# trig3_board.net
KiCad netlist of a schematic drawn in EAGLE
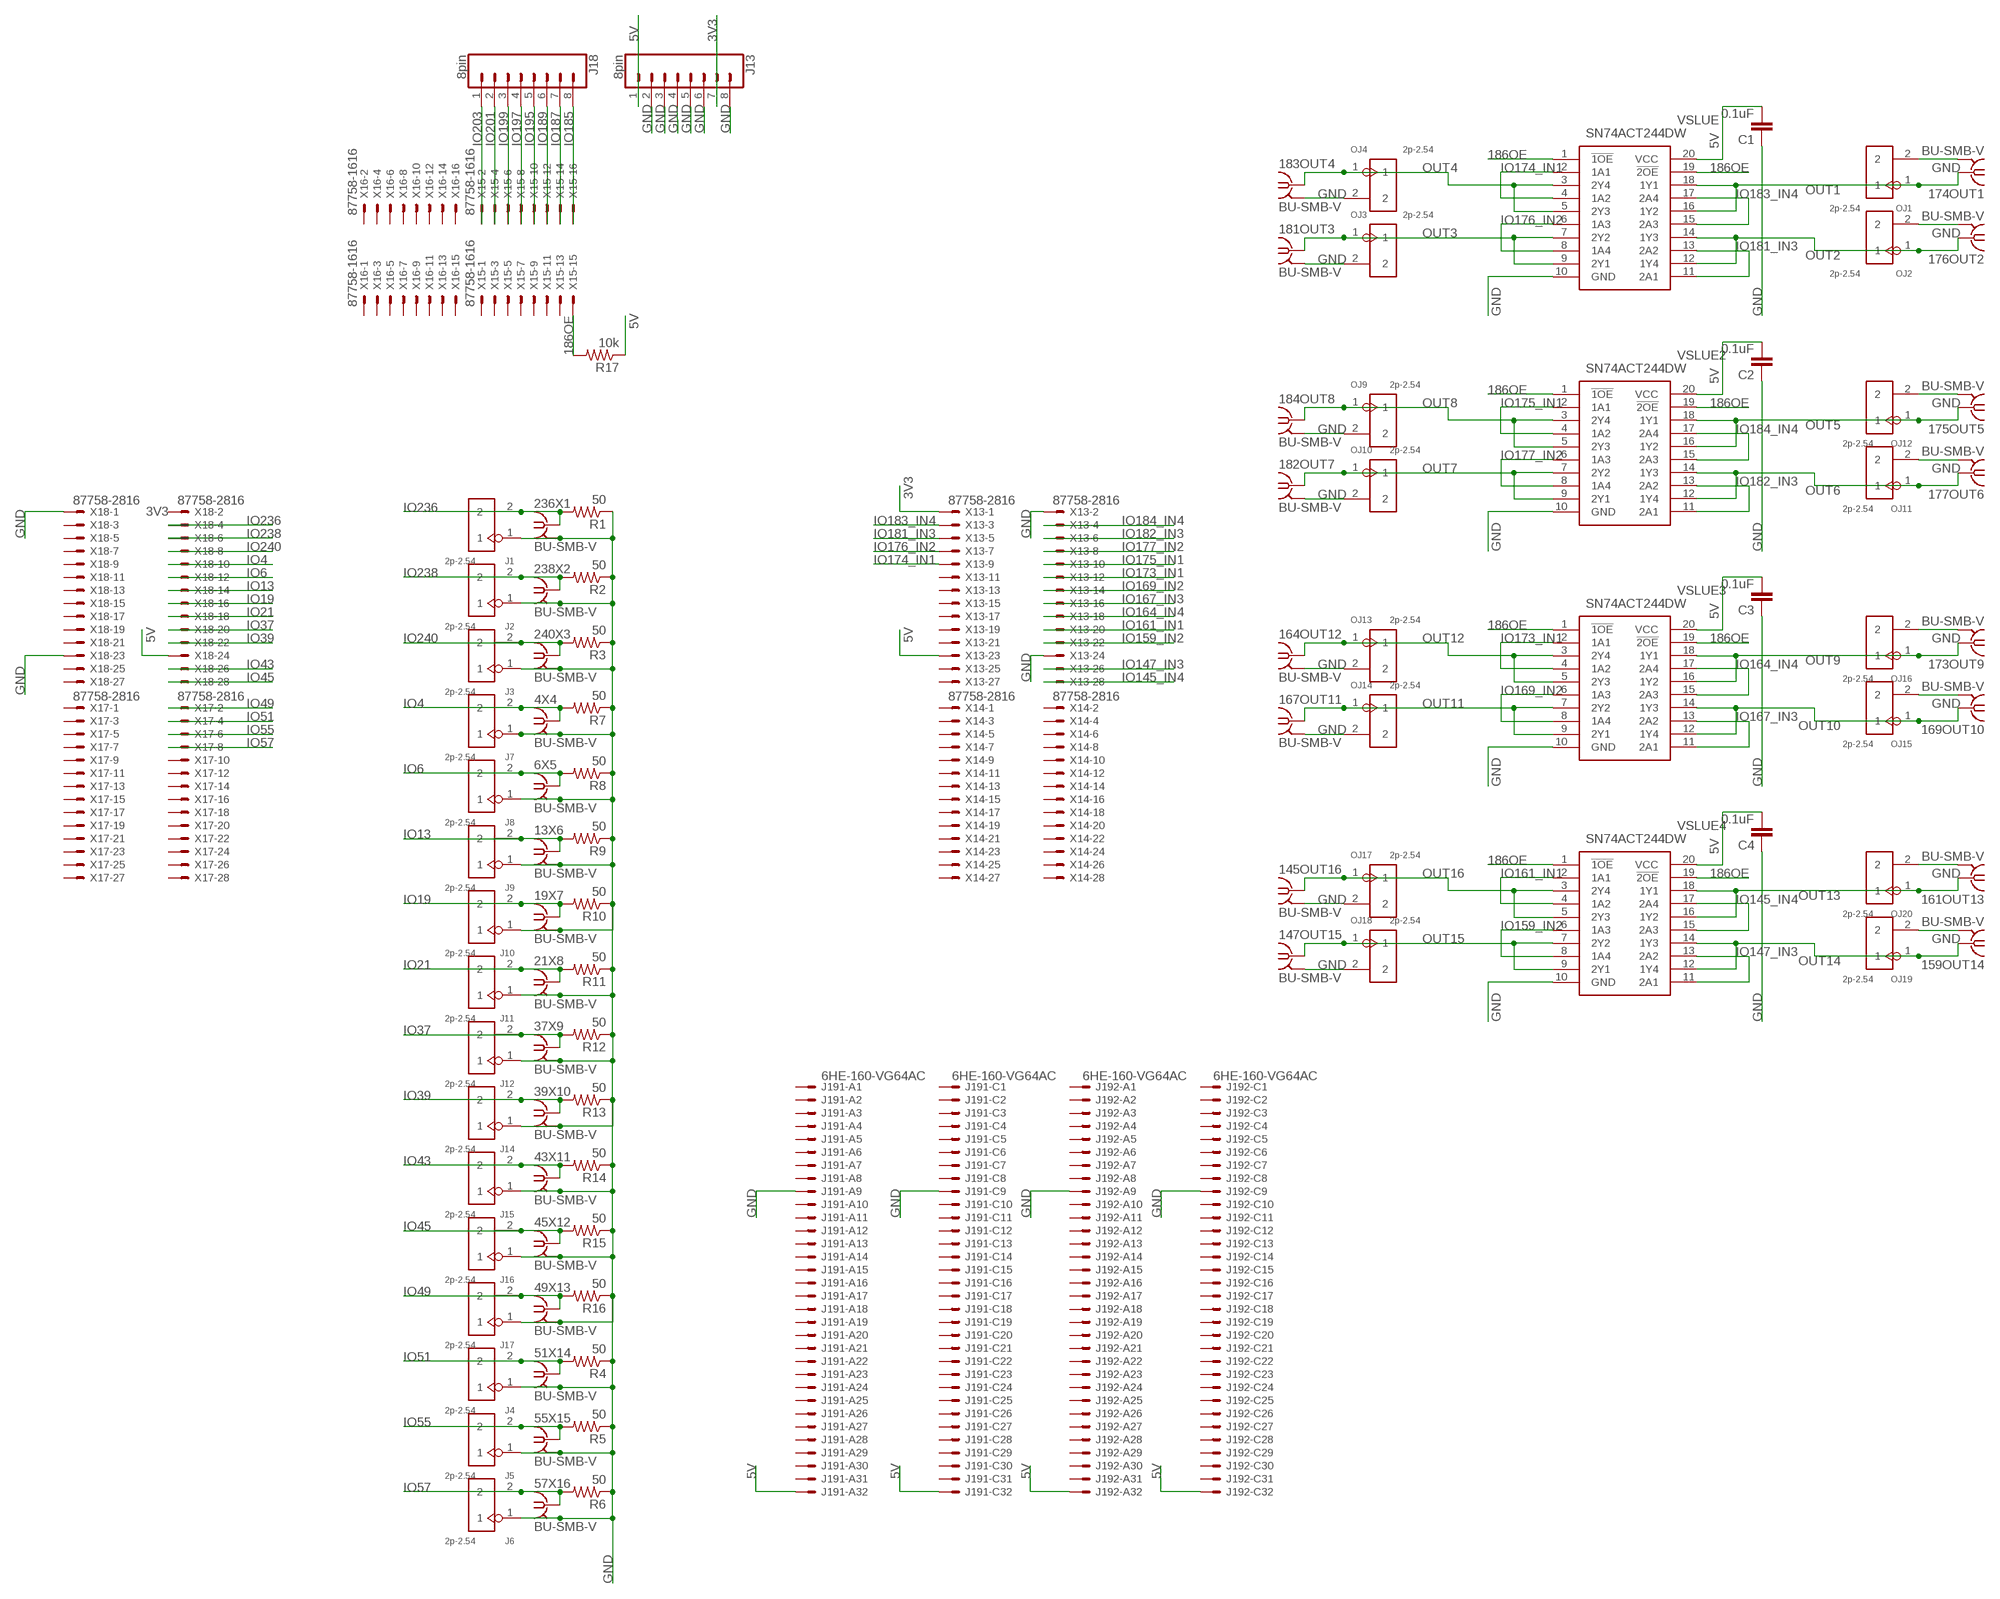
[diagram p0: schematic, sheet 1]

(export (version "E")
  (design (tool "Eeschema 10.0.6"))
  (components
    (comp (ref "4X4")
      (value "BU-SMB-V")
      (footprint "eagle-import:BU-SMB-V")
      (libsource (lib "eagle-import") (part "BU-SMB-V"))
    )
    (comp (ref "6X5")
      (value "BU-SMB-V")
      (footprint "eagle-import:BU-SMB-V")
      (libsource (lib "eagle-import") (part "BU-SMB-V"))
    )
    (comp (ref "13X6")
      (value "BU-SMB-V")
      (footprint "eagle-import:BU-SMB-V")
      (libsource (lib "eagle-import") (part "BU-SMB-V"))
    )
    (comp (ref "19X7")
      (value "BU-SMB-V")
      (footprint "eagle-import:BU-SMB-V")
      (libsource (lib "eagle-import") (part "BU-SMB-V"))
    )
    (comp (ref "21X8")
      (value "BU-SMB-V")
      (footprint "eagle-import:BU-SMB-V")
      (libsource (lib "eagle-import") (part "BU-SMB-V"))
    )
    (comp (ref "37X9")
      (value "BU-SMB-V")
      (footprint "eagle-import:BU-SMB-V")
      (libsource (lib "eagle-import") (part "BU-SMB-V"))
    )
    (comp (ref "39X10")
      (value "BU-SMB-V")
      (footprint "eagle-import:BU-SMB-V")
      (libsource (lib "eagle-import") (part "BU-SMB-V"))
    )
    (comp (ref "43X11")
      (value "BU-SMB-V")
      (footprint "eagle-import:BU-SMB-V")
      (libsource (lib "eagle-import") (part "BU-SMB-V"))
    )
    (comp (ref "45X12")
      (value "BU-SMB-V")
      (footprint "eagle-import:BU-SMB-V")
      (libsource (lib "eagle-import") (part "BU-SMB-V"))
    )
    (comp (ref "49X13")
      (value "BU-SMB-V")
      (footprint "eagle-import:BU-SMB-V")
      (libsource (lib "eagle-import") (part "BU-SMB-V"))
    )
    (comp (ref "51X14")
      (value "BU-SMB-V")
      (footprint "eagle-import:BU-SMB-V")
      (libsource (lib "eagle-import") (part "BU-SMB-V"))
    )
    (comp (ref "55X15")
      (value "BU-SMB-V")
      (footprint "eagle-import:BU-SMB-V")
      (libsource (lib "eagle-import") (part "BU-SMB-V"))
    )
    (comp (ref "57X16")
      (value "BU-SMB-V")
      (footprint "eagle-import:BU-SMB-V")
      (libsource (lib "eagle-import") (part "BU-SMB-V"))
    )
    (comp (ref "145OUT16")
      (value "BU-SMB-V")
      (footprint "eagle-import:BU-SMB-V")
      (libsource (lib "eagle-import") (part "BU-SMB-V"))
    )
    (comp (ref "147OUT15")
      (value "BU-SMB-V")
      (footprint "eagle-import:BU-SMB-V")
      (libsource (lib "eagle-import") (part "BU-SMB-V"))
    )
    (comp (ref "159OUT14")
      (value "BU-SMB-V")
      (footprint "eagle-import:BU-SMB-V")
      (libsource (lib "eagle-import") (part "BU-SMB-V"))
    )
    (comp (ref "161OUT13")
      (value "BU-SMB-V")
      (footprint "eagle-import:BU-SMB-V")
      (libsource (lib "eagle-import") (part "BU-SMB-V"))
    )
    (comp (ref "164OUT12")
      (value "BU-SMB-V")
      (footprint "eagle-import:BU-SMB-V")
      (libsource (lib "eagle-import") (part "BU-SMB-V"))
    )
    (comp (ref "167OUT11")
      (value "BU-SMB-V")
      (footprint "eagle-import:BU-SMB-V")
      (libsource (lib "eagle-import") (part "BU-SMB-V"))
    )
    (comp (ref "169OUT10")
      (value "BU-SMB-V")
      (footprint "eagle-import:BU-SMB-V")
      (libsource (lib "eagle-import") (part "BU-SMB-V"))
    )
    (comp (ref "173OUT9")
      (value "BU-SMB-V")
      (footprint "eagle-import:BU-SMB-V")
      (libsource (lib "eagle-import") (part "BU-SMB-V"))
    )
    (comp (ref "174OUT1")
      (value "BU-SMB-V")
      (footprint "eagle-import:BU-SMB-V")
      (libsource (lib "eagle-import") (part "BU-SMB-V"))
    )
    (comp (ref "175OUT5")
      (value "BU-SMB-V")
      (footprint "eagle-import:BU-SMB-V")
      (libsource (lib "eagle-import") (part "BU-SMB-V"))
    )
    (comp (ref "176OUT2")
      (value "BU-SMB-V")
      (footprint "eagle-import:BU-SMB-V")
      (libsource (lib "eagle-import") (part "BU-SMB-V"))
    )
    (comp (ref "177OUT6")
      (value "BU-SMB-V")
      (footprint "eagle-import:BU-SMB-V")
      (libsource (lib "eagle-import") (part "BU-SMB-V"))
    )
    (comp (ref "181OUT3")
      (value "BU-SMB-V")
      (footprint "eagle-import:BU-SMB-V")
      (libsource (lib "eagle-import") (part "BU-SMB-V"))
    )
    (comp (ref "182OUT7")
      (value "BU-SMB-V")
      (footprint "eagle-import:BU-SMB-V")
      (libsource (lib "eagle-import") (part "BU-SMB-V"))
    )
    (comp (ref "183OUT4")
      (value "BU-SMB-V")
      (footprint "eagle-import:BU-SMB-V")
      (libsource (lib "eagle-import") (part "BU-SMB-V"))
    )
    (comp (ref "184OUT8")
      (value "BU-SMB-V")
      (footprint "eagle-import:BU-SMB-V")
      (libsource (lib "eagle-import") (part "BU-SMB-V"))
    )
    (comp (ref "236X1")
      (value "BU-SMB-V")
      (footprint "eagle-import:BU-SMB-V")
      (libsource (lib "eagle-import") (part "BU-SMB-V"))
    )
    (comp (ref "238X2")
      (value "BU-SMB-V")
      (footprint "eagle-import:BU-SMB-V")
      (libsource (lib "eagle-import") (part "BU-SMB-V"))
    )
    (comp (ref "240X3")
      (value "BU-SMB-V")
      (footprint "eagle-import:BU-SMB-V")
      (libsource (lib "eagle-import") (part "BU-SMB-V"))
    )
    (comp (ref "C1")
      (value "0.1uF")
      (footprint "eagle-import:0805")
      (libsource (lib "eagle-import") (part "CAP0805"))
    )
    (comp (ref "C2")
      (value "0.1uF")
      (footprint "eagle-import:0805")
      (libsource (lib "eagle-import") (part "CAP0805"))
    )
    (comp (ref "C3")
      (value "0.1uF")
      (footprint "eagle-import:0805")
      (libsource (lib "eagle-import") (part "CAP0805"))
    )
    (comp (ref "C4")
      (value "0.1uF")
      (footprint "eagle-import:0805")
      (libsource (lib "eagle-import") (part "CAP0805"))
    )
    (comp (ref "J1")
      (value "2p-2.54")
      (footprint "eagle-import:H2-2.54")
      (fields (field (name "MPN") "P125-1102A0BS116A1"))
      (libsource (lib "eagle-import") (part "DIP-BLACK-MALE-HEADER-VERT(2P-2.54)"))
    )
    (comp (ref "J2")
      (value "2p-2.54")
      (footprint "eagle-import:H2-2.54")
      (fields (field (name "MPN") "P125-1102A0BS116A1"))
      (libsource (lib "eagle-import") (part "DIP-BLACK-MALE-HEADER-VERT(2P-2.54)"))
    )
    (comp (ref "J3")
      (value "2p-2.54")
      (footprint "eagle-import:H2-2.54")
      (fields (field (name "MPN") "P125-1102A0BS116A1"))
      (libsource (lib "eagle-import") (part "DIP-BLACK-MALE-HEADER-VERT(2P-2.54)"))
    )
    (comp (ref "J4")
      (value "2p-2.54")
      (footprint "eagle-import:H2-2.54")
      (fields (field (name "MPN") "P125-1102A0BS116A1"))
      (libsource (lib "eagle-import") (part "DIP-BLACK-MALE-HEADER-VERT(2P-2.54)"))
    )
    (comp (ref "J5")
      (value "2p-2.54")
      (footprint "eagle-import:H2-2.54")
      (fields (field (name "MPN") "P125-1102A0BS116A1"))
      (libsource (lib "eagle-import") (part "DIP-BLACK-MALE-HEADER-VERT(2P-2.54)"))
    )
    (comp (ref "J6")
      (value "2p-2.54")
      (footprint "eagle-import:H2-2.54")
      (fields (field (name "MPN") "P125-1102A0BS116A1"))
      (libsource (lib "eagle-import") (part "DIP-BLACK-MALE-HEADER-VERT(2P-2.54)"))
    )
    (comp (ref "J7")
      (value "2p-2.54")
      (footprint "eagle-import:H2-2.54")
      (fields (field (name "MPN") "P125-1102A0BS116A1"))
      (libsource (lib "eagle-import") (part "DIP-BLACK-MALE-HEADER-VERT(2P-2.54)"))
    )
    (comp (ref "J8")
      (value "2p-2.54")
      (footprint "eagle-import:H2-2.54")
      (fields (field (name "MPN") "P125-1102A0BS116A1"))
      (libsource (lib "eagle-import") (part "DIP-BLACK-MALE-HEADER-VERT(2P-2.54)"))
    )
    (comp (ref "J9")
      (value "2p-2.54")
      (footprint "eagle-import:H2-2.54")
      (fields (field (name "MPN") "P125-1102A0BS116A1"))
      (libsource (lib "eagle-import") (part "DIP-BLACK-MALE-HEADER-VERT(2P-2.54)"))
    )
    (comp (ref "J10")
      (value "2p-2.54")
      (footprint "eagle-import:H2-2.54")
      (fields (field (name "MPN") "P125-1102A0BS116A1"))
      (libsource (lib "eagle-import") (part "DIP-BLACK-MALE-HEADER-VERT(2P-2.54)"))
    )
    (comp (ref "J11")
      (value "2p-2.54")
      (footprint "eagle-import:H2-2.54")
      (fields (field (name "MPN") "P125-1102A0BS116A1"))
      (libsource (lib "eagle-import") (part "DIP-BLACK-MALE-HEADER-VERT(2P-2.54)"))
    )
    (comp (ref "J12")
      (value "2p-2.54")
      (footprint "eagle-import:H2-2.54")
      (fields (field (name "MPN") "P125-1102A0BS116A1"))
      (libsource (lib "eagle-import") (part "DIP-BLACK-MALE-HEADER-VERT(2P-2.54)"))
    )
    (comp (ref "J13")
      (value "8pin")
      (footprint "eagle-import:1X08")
      (libsource (lib "eagle-import") (part "CONN_08{dblquote}"))
    )
    (comp (ref "J14")
      (value "2p-2.54")
      (footprint "eagle-import:H2-2.54")
      (fields (field (name "MPN") "P125-1102A0BS116A1"))
      (libsource (lib "eagle-import") (part "DIP-BLACK-MALE-HEADER-VERT(2P-2.54)"))
    )
    (comp (ref "J15")
      (value "2p-2.54")
      (footprint "eagle-import:H2-2.54")
      (fields (field (name "MPN") "P125-1102A0BS116A1"))
      (libsource (lib "eagle-import") (part "DIP-BLACK-MALE-HEADER-VERT(2P-2.54)"))
    )
    (comp (ref "J16")
      (value "2p-2.54")
      (footprint "eagle-import:H2-2.54")
      (fields (field (name "MPN") "P125-1102A0BS116A1"))
      (libsource (lib "eagle-import") (part "DIP-BLACK-MALE-HEADER-VERT(2P-2.54)"))
    )
    (comp (ref "J17")
      (value "2p-2.54")
      (footprint "eagle-import:H2-2.54")
      (fields (field (name "MPN") "P125-1102A0BS116A1"))
      (libsource (lib "eagle-import") (part "DIP-BLACK-MALE-HEADER-VERT(2P-2.54)"))
    )
    (comp (ref "J18")
      (value "8pin")
      (footprint "eagle-import:1X08")
      (libsource (lib "eagle-import") (part "CONN_08{dblquote}"))
    )
    (comp (ref "J19")
      (value "6HE-160-VG64AC")
      (footprint "eagle-import:6HE_160-VG64AC")
      (libsource (lib "eagle-import") (part "6HE-?-VG64AC160"))
    )
    (comp (ref "OJ1")
      (value "2p-2.54")
      (footprint "eagle-import:H2-2.54")
      (fields (field (name "MPN") "P125-1102A0BS116A1"))
      (libsource (lib "eagle-import") (part "DIP-BLACK-MALE-HEADER-VERT(2P-2.54)"))
    )
    (comp (ref "OJ2")
      (value "2p-2.54")
      (footprint "eagle-import:H2-2.54")
      (fields (field (name "MPN") "P125-1102A0BS116A1"))
      (libsource (lib "eagle-import") (part "DIP-BLACK-MALE-HEADER-VERT(2P-2.54)"))
    )
    (comp (ref "OJ3")
      (value "2p-2.54")
      (footprint "eagle-import:H2-2.54")
      (fields (field (name "MPN") "P125-1102A0BS116A1"))
      (libsource (lib "eagle-import") (part "DIP-BLACK-MALE-HEADER-VERT(2P-2.54)"))
    )
    (comp (ref "OJ4")
      (value "2p-2.54")
      (footprint "eagle-import:H2-2.54")
      (fields (field (name "MPN") "P125-1102A0BS116A1"))
      (libsource (lib "eagle-import") (part "DIP-BLACK-MALE-HEADER-VERT(2P-2.54)"))
    )
    (comp (ref "OJ9")
      (value "2p-2.54")
      (footprint "eagle-import:H2-2.54")
      (fields (field (name "MPN") "P125-1102A0BS116A1"))
      (libsource (lib "eagle-import") (part "DIP-BLACK-MALE-HEADER-VERT(2P-2.54)"))
    )
    (comp (ref "OJ10")
      (value "2p-2.54")
      (footprint "eagle-import:H2-2.54")
      (fields (field (name "MPN") "P125-1102A0BS116A1"))
      (libsource (lib "eagle-import") (part "DIP-BLACK-MALE-HEADER-VERT(2P-2.54)"))
    )
    (comp (ref "OJ11")
      (value "2p-2.54")
      (footprint "eagle-import:H2-2.54")
      (fields (field (name "MPN") "P125-1102A0BS116A1"))
      (libsource (lib "eagle-import") (part "DIP-BLACK-MALE-HEADER-VERT(2P-2.54)"))
    )
    (comp (ref "OJ12")
      (value "2p-2.54")
      (footprint "eagle-import:H2-2.54")
      (fields (field (name "MPN") "P125-1102A0BS116A1"))
      (libsource (lib "eagle-import") (part "DIP-BLACK-MALE-HEADER-VERT(2P-2.54)"))
    )
    (comp (ref "OJ13")
      (value "2p-2.54")
      (footprint "eagle-import:H2-2.54")
      (fields (field (name "MPN") "P125-1102A0BS116A1"))
      (libsource (lib "eagle-import") (part "DIP-BLACK-MALE-HEADER-VERT(2P-2.54)"))
    )
    (comp (ref "OJ14")
      (value "2p-2.54")
      (footprint "eagle-import:H2-2.54")
      (fields (field (name "MPN") "P125-1102A0BS116A1"))
      (libsource (lib "eagle-import") (part "DIP-BLACK-MALE-HEADER-VERT(2P-2.54)"))
    )
    (comp (ref "OJ15")
      (value "2p-2.54")
      (footprint "eagle-import:H2-2.54")
      (fields (field (name "MPN") "P125-1102A0BS116A1"))
      (libsource (lib "eagle-import") (part "DIP-BLACK-MALE-HEADER-VERT(2P-2.54)"))
    )
    (comp (ref "OJ16")
      (value "2p-2.54")
      (footprint "eagle-import:H2-2.54")
      (fields (field (name "MPN") "P125-1102A0BS116A1"))
      (libsource (lib "eagle-import") (part "DIP-BLACK-MALE-HEADER-VERT(2P-2.54)"))
    )
    (comp (ref "OJ17")
      (value "2p-2.54")
      (footprint "eagle-import:H2-2.54")
      (fields (field (name "MPN") "P125-1102A0BS116A1"))
      (libsource (lib "eagle-import") (part "DIP-BLACK-MALE-HEADER-VERT(2P-2.54)"))
    )
    (comp (ref "OJ18")
      (value "2p-2.54")
      (footprint "eagle-import:H2-2.54")
      (fields (field (name "MPN") "P125-1102A0BS116A1"))
      (libsource (lib "eagle-import") (part "DIP-BLACK-MALE-HEADER-VERT(2P-2.54)"))
    )
    (comp (ref "OJ19")
      (value "2p-2.54")
      (footprint "eagle-import:H2-2.54")
      (fields (field (name "MPN") "P125-1102A0BS116A1"))
      (libsource (lib "eagle-import") (part "DIP-BLACK-MALE-HEADER-VERT(2P-2.54)"))
    )
    (comp (ref "OJ20")
      (value "2p-2.54")
      (footprint "eagle-import:H2-2.54")
      (fields (field (name "MPN") "P125-1102A0BS116A1"))
      (libsource (lib "eagle-import") (part "DIP-BLACK-MALE-HEADER-VERT(2P-2.54)"))
    )
    (comp (ref "R1")
      (value "50")
      (footprint "eagle-import:AXIAL-0.3")
      (libsource (lib "eagle-import") (part "RESISTORAXIAL-0.3"))
    )
    (comp (ref "R2")
      (value "50")
      (footprint "eagle-import:AXIAL-0.3")
      (libsource (lib "eagle-import") (part "RESISTORAXIAL-0.3"))
    )
    (comp (ref "R3")
      (value "50")
      (footprint "eagle-import:AXIAL-0.3")
      (libsource (lib "eagle-import") (part "RESISTORAXIAL-0.3"))
    )
    (comp (ref "R4")
      (value "50")
      (footprint "eagle-import:AXIAL-0.3")
      (libsource (lib "eagle-import") (part "RESISTORAXIAL-0.3"))
    )
    (comp (ref "R5")
      (value "50")
      (footprint "eagle-import:AXIAL-0.3")
      (libsource (lib "eagle-import") (part "RESISTORAXIAL-0.3"))
    )
    (comp (ref "R6")
      (value "50")
      (footprint "eagle-import:AXIAL-0.3")
      (libsource (lib "eagle-import") (part "RESISTORAXIAL-0.3"))
    )
    (comp (ref "R7")
      (value "50")
      (footprint "eagle-import:AXIAL-0.3")
      (libsource (lib "eagle-import") (part "RESISTORAXIAL-0.3"))
    )
    (comp (ref "R8")
      (value "50")
      (footprint "eagle-import:AXIAL-0.3")
      (libsource (lib "eagle-import") (part "RESISTORAXIAL-0.3"))
    )
    (comp (ref "R9")
      (value "50")
      (footprint "eagle-import:AXIAL-0.3")
      (libsource (lib "eagle-import") (part "RESISTORAXIAL-0.3"))
    )
    (comp (ref "R10")
      (value "50")
      (footprint "eagle-import:AXIAL-0.3")
      (libsource (lib "eagle-import") (part "RESISTORAXIAL-0.3"))
    )
    (comp (ref "R11")
      (value "50")
      (footprint "eagle-import:AXIAL-0.3")
      (libsource (lib "eagle-import") (part "RESISTORAXIAL-0.3"))
    )
    (comp (ref "R12")
      (value "50")
      (footprint "eagle-import:AXIAL-0.3")
      (libsource (lib "eagle-import") (part "RESISTORAXIAL-0.3"))
    )
    (comp (ref "R13")
      (value "50")
      (footprint "eagle-import:AXIAL-0.3")
      (libsource (lib "eagle-import") (part "RESISTORAXIAL-0.3"))
    )
    (comp (ref "R14")
      (value "50")
      (footprint "eagle-import:AXIAL-0.3")
      (libsource (lib "eagle-import") (part "RESISTORAXIAL-0.3"))
    )
    (comp (ref "R15")
      (value "50")
      (footprint "eagle-import:AXIAL-0.3")
      (libsource (lib "eagle-import") (part "RESISTORAXIAL-0.3"))
    )
    (comp (ref "R16")
      (value "50")
      (footprint "eagle-import:AXIAL-0.3")
      (libsource (lib "eagle-import") (part "RESISTORAXIAL-0.3"))
    )
    (comp (ref "R17")
      (value "10k")
      (footprint "eagle-import:AXIAL-0.3")
      (libsource (lib "eagle-import") (part "RESISTORAXIAL-0.3"))
    )
    (comp (ref "VSLUE")
      (value "SN74ACT244DW")
      (footprint "eagle-import:SOIC127P1030X265-20N")
      (fields (field (name "RS_PART_NUMBER") "4363169"))
      (libsource (lib "eagle-import") (part "SN74ACT244DW"))
    )
    (comp (ref "VSLUE2")
      (value "SN74ACT244DW")
      (footprint "eagle-import:SOIC127P1030X265-20N")
      (fields (field (name "RS_PART_NUMBER") "4363169"))
      (libsource (lib "eagle-import") (part "SN74ACT244DW"))
    )
    (comp (ref "VSLUE3")
      (value "SN74ACT244DW")
      (footprint "eagle-import:SOIC127P1030X265-20N")
      (fields (field (name "RS_PART_NUMBER") "4363169"))
      (libsource (lib "eagle-import") (part "SN74ACT244DW"))
    )
    (comp (ref "VSLUE4")
      (value "SN74ACT244DW")
      (footprint "eagle-import:SOIC127P1030X265-20N")
      (fields (field (name "RS_PART_NUMBER") "4363169"))
      (libsource (lib "eagle-import") (part "SN74ACT244DW"))
    )
    (comp (ref "X13")
      (value "87758-2816")
      (footprint "eagle-import:87758-2816")
      (fields (field (name "MF") "MOLEX"))
      (libsource (lib "eagle-import") (part "87758-2816"))
    )
    (comp (ref "X14")
      (value "87758-2816")
      (footprint "eagle-import:87758-2816")
      (fields (field (name "MF") "MOLEX"))
      (libsource (lib "eagle-import") (part "87758-2816"))
    )
    (comp (ref "X15")
      (value "87758-1616")
      (footprint "eagle-import:87758-1616")
      (fields (field (name "MF") "MOLEX"))
      (libsource (lib "eagle-import") (part "87758-1616"))
    )
    (comp (ref "X16")
      (value "87758-1616")
      (footprint "eagle-import:87758-1616")
      (fields (field (name "MF") "MOLEX"))
      (libsource (lib "eagle-import") (part "87758-1616"))
    )
    (comp (ref "X17")
      (value "87758-2816")
      (footprint "eagle-import:87758-2816")
      (fields (field (name "MF") "MOLEX"))
      (libsource (lib "eagle-import") (part "87758-2816"))
    )
    (comp (ref "X18")
      (value "87758-2816")
      (footprint "eagle-import:87758-2816")
      (fields (field (name "MF") "MOLEX"))
      (libsource (lib "eagle-import") (part "87758-2816"))
    )
  )
  (nets
    (net (code "1") (name "/3V3") (class "Default")
      (node (ref "J13") (pin "7") (pinfunction "7_7") (pintype "passive"))
      (node (ref "X13") (pin "1") (pinfunction "S_1") (pintype "passive"))
    )
    (net (code "2") (name "/5V") (class "Default")
      (node (ref "C1") (pin "2") (pinfunction "2_2") (pintype "passive"))
      (node (ref "C2") (pin "2") (pinfunction "2_2") (pintype "passive"))
      (node (ref "C3") (pin "2") (pinfunction "2_2") (pintype "passive"))
      (node (ref "C4") (pin "2") (pinfunction "2_2") (pintype "passive"))
      (node (ref "J13") (pin "1") (pinfunction "1_1") (pintype "passive"))
      (node (ref "J19") (pin "1-A32") (pinfunction "MS_1-A32") (pintype "passive"))
      (node (ref "J19") (pin "1-C32") (pinfunction "MS_1-C32") (pintype "passive"))
      (node (ref "J19") (pin "2-A32") (pinfunction "MS_2-A32") (pintype "passive"))
      (node (ref "J19") (pin "2-C32") (pinfunction "MS_2-C32") (pintype "passive"))
      (node (ref "R17") (pin "P$1") (pinfunction "1_P$1") (pintype "passive"))
      (node (ref "VSLUE") (pin "20") (pinfunction "VCC_20") (pintype "power_in"))
      (node (ref "VSLUE2") (pin "20") (pinfunction "VCC_20") (pintype "power_in"))
      (node (ref "VSLUE3") (pin "20") (pinfunction "VCC_20") (pintype "power_in"))
      (node (ref "VSLUE4") (pin "20") (pinfunction "VCC_20") (pintype "power_in"))
      (node (ref "X13") (pin "23") (pinfunction "S_23") (pintype "passive"))
      (node (ref "X18") (pin "24") (pinfunction "S_24") (pintype "passive"))
    )
    (net (code "3") (name "/186OE") (class "Default")
      (node (ref "R17") (pin "P$2") (pinfunction "2_P$2") (pintype "passive"))
      (node (ref "VSLUE") (pin "1") (pinfunction "~{1OE}_1") (pintype "input"))
      (node (ref "VSLUE") (pin "19") (pinfunction "~{2OE}_19") (pintype "input"))
      (node (ref "VSLUE2") (pin "1") (pinfunction "~{1OE}_1") (pintype "input"))
      (node (ref "VSLUE2") (pin "19") (pinfunction "~{2OE}_19") (pintype "input"))
      (node (ref "VSLUE3") (pin "1") (pinfunction "~{1OE}_1") (pintype "input"))
      (node (ref "VSLUE3") (pin "19") (pinfunction "~{2OE}_19") (pintype "input"))
      (node (ref "VSLUE4") (pin "1") (pinfunction "~{1OE}_1") (pintype "input"))
      (node (ref "VSLUE4") (pin "19") (pinfunction "~{2OE}_19") (pintype "input"))
      (node (ref "X15") (pin "15") (pinfunction "S_15") (pintype "passive"))
    )
    (net (code "4") (name "/GND") (class "Default")
      (node (ref "13X6") (pin "2") (pinfunction "2_2") (pintype "passive"))
      (node (ref "13X6") (pin "3") (pinfunction "2_3") (pintype "passive"))
      (node (ref "13X6") (pin "4") (pinfunction "2_4") (pintype "passive"))
      (node (ref "13X6") (pin "5") (pinfunction "2_5") (pintype "passive"))
      (node (ref "145OUT16") (pin "2") (pinfunction "2_2") (pintype "passive"))
      (node (ref "145OUT16") (pin "3") (pinfunction "2_3") (pintype "passive"))
      (node (ref "145OUT16") (pin "4") (pinfunction "2_4") (pintype "passive"))
      (node (ref "145OUT16") (pin "5") (pinfunction "2_5") (pintype "passive"))
      (node (ref "147OUT15") (pin "2") (pinfunction "2_2") (pintype "passive"))
      (node (ref "147OUT15") (pin "3") (pinfunction "2_3") (pintype "passive"))
      (node (ref "147OUT15") (pin "4") (pinfunction "2_4") (pintype "passive"))
      (node (ref "147OUT15") (pin "5") (pinfunction "2_5") (pintype "passive"))
      (node (ref "159OUT14") (pin "2") (pinfunction "2_2") (pintype "passive"))
      (node (ref "159OUT14") (pin "3") (pinfunction "2_3") (pintype "passive"))
      (node (ref "159OUT14") (pin "4") (pinfunction "2_4") (pintype "passive"))
      (node (ref "159OUT14") (pin "5") (pinfunction "2_5") (pintype "passive"))
      (node (ref "161OUT13") (pin "2") (pinfunction "2_2") (pintype "passive"))
      (node (ref "161OUT13") (pin "3") (pinfunction "2_3") (pintype "passive"))
      (node (ref "161OUT13") (pin "4") (pinfunction "2_4") (pintype "passive"))
      (node (ref "161OUT13") (pin "5") (pinfunction "2_5") (pintype "passive"))
      (node (ref "164OUT12") (pin "2") (pinfunction "2_2") (pintype "passive"))
      (node (ref "164OUT12") (pin "3") (pinfunction "2_3") (pintype "passive"))
      (node (ref "164OUT12") (pin "4") (pinfunction "2_4") (pintype "passive"))
      (node (ref "164OUT12") (pin "5") (pinfunction "2_5") (pintype "passive"))
      (node (ref "167OUT11") (pin "2") (pinfunction "2_2") (pintype "passive"))
      (node (ref "167OUT11") (pin "3") (pinfunction "2_3") (pintype "passive"))
      (node (ref "167OUT11") (pin "4") (pinfunction "2_4") (pintype "passive"))
      (node (ref "167OUT11") (pin "5") (pinfunction "2_5") (pintype "passive"))
      (node (ref "169OUT10") (pin "2") (pinfunction "2_2") (pintype "passive"))
      (node (ref "169OUT10") (pin "3") (pinfunction "2_3") (pintype "passive"))
      (node (ref "169OUT10") (pin "4") (pinfunction "2_4") (pintype "passive"))
      (node (ref "169OUT10") (pin "5") (pinfunction "2_5") (pintype "passive"))
      (node (ref "173OUT9") (pin "2") (pinfunction "2_2") (pintype "passive"))
      (node (ref "173OUT9") (pin "3") (pinfunction "2_3") (pintype "passive"))
      (node (ref "173OUT9") (pin "4") (pinfunction "2_4") (pintype "passive"))
      (node (ref "173OUT9") (pin "5") (pinfunction "2_5") (pintype "passive"))
      (node (ref "174OUT1") (pin "2") (pinfunction "2_2") (pintype "passive"))
      (node (ref "174OUT1") (pin "3") (pinfunction "2_3") (pintype "passive"))
      (node (ref "174OUT1") (pin "4") (pinfunction "2_4") (pintype "passive"))
      (node (ref "174OUT1") (pin "5") (pinfunction "2_5") (pintype "passive"))
      (node (ref "175OUT5") (pin "2") (pinfunction "2_2") (pintype "passive"))
      (node (ref "175OUT5") (pin "3") (pinfunction "2_3") (pintype "passive"))
      (node (ref "175OUT5") (pin "4") (pinfunction "2_4") (pintype "passive"))
      (node (ref "175OUT5") (pin "5") (pinfunction "2_5") (pintype "passive"))
      (node (ref "176OUT2") (pin "2") (pinfunction "2_2") (pintype "passive"))
      (node (ref "176OUT2") (pin "3") (pinfunction "2_3") (pintype "passive"))
      (node (ref "176OUT2") (pin "4") (pinfunction "2_4") (pintype "passive"))
      (node (ref "176OUT2") (pin "5") (pinfunction "2_5") (pintype "passive"))
      (node (ref "177OUT6") (pin "2") (pinfunction "2_2") (pintype "passive"))
      (node (ref "177OUT6") (pin "3") (pinfunction "2_3") (pintype "passive"))
      (node (ref "177OUT6") (pin "4") (pinfunction "2_4") (pintype "passive"))
      (node (ref "177OUT6") (pin "5") (pinfunction "2_5") (pintype "passive"))
      (node (ref "181OUT3") (pin "2") (pinfunction "2_2") (pintype "passive"))
      (node (ref "181OUT3") (pin "3") (pinfunction "2_3") (pintype "passive"))
      (node (ref "181OUT3") (pin "4") (pinfunction "2_4") (pintype "passive"))
      (node (ref "181OUT3") (pin "5") (pinfunction "2_5") (pintype "passive"))
      (node (ref "182OUT7") (pin "2") (pinfunction "2_2") (pintype "passive"))
      (node (ref "182OUT7") (pin "3") (pinfunction "2_3") (pintype "passive"))
      (node (ref "182OUT7") (pin "4") (pinfunction "2_4") (pintype "passive"))
      (node (ref "182OUT7") (pin "5") (pinfunction "2_5") (pintype "passive"))
      (node (ref "183OUT4") (pin "2") (pinfunction "2_2") (pintype "passive"))
      (node (ref "183OUT4") (pin "3") (pinfunction "2_3") (pintype "passive"))
      (node (ref "183OUT4") (pin "4") (pinfunction "2_4") (pintype "passive"))
      (node (ref "183OUT4") (pin "5") (pinfunction "2_5") (pintype "passive"))
      (node (ref "184OUT8") (pin "2") (pinfunction "2_2") (pintype "passive"))
      (node (ref "184OUT8") (pin "3") (pinfunction "2_3") (pintype "passive"))
      (node (ref "184OUT8") (pin "4") (pinfunction "2_4") (pintype "passive"))
      (node (ref "184OUT8") (pin "5") (pinfunction "2_5") (pintype "passive"))
      (node (ref "19X7") (pin "2") (pinfunction "2_2") (pintype "passive"))
      (node (ref "19X7") (pin "3") (pinfunction "2_3") (pintype "passive"))
      (node (ref "19X7") (pin "4") (pinfunction "2_4") (pintype "passive"))
      (node (ref "19X7") (pin "5") (pinfunction "2_5") (pintype "passive"))
      (node (ref "21X8") (pin "2") (pinfunction "2_2") (pintype "passive"))
      (node (ref "21X8") (pin "3") (pinfunction "2_3") (pintype "passive"))
      (node (ref "21X8") (pin "4") (pinfunction "2_4") (pintype "passive"))
      (node (ref "21X8") (pin "5") (pinfunction "2_5") (pintype "passive"))
      (node (ref "236X1") (pin "2") (pinfunction "2_2") (pintype "passive"))
      (node (ref "236X1") (pin "3") (pinfunction "2_3") (pintype "passive"))
      (node (ref "236X1") (pin "4") (pinfunction "2_4") (pintype "passive"))
      (node (ref "236X1") (pin "5") (pinfunction "2_5") (pintype "passive"))
      (node (ref "238X2") (pin "2") (pinfunction "2_2") (pintype "passive"))
      (node (ref "238X2") (pin "3") (pinfunction "2_3") (pintype "passive"))
      (node (ref "238X2") (pin "4") (pinfunction "2_4") (pintype "passive"))
      (node (ref "238X2") (pin "5") (pinfunction "2_5") (pintype "passive"))
      (node (ref "240X3") (pin "2") (pinfunction "2_2") (pintype "passive"))
      (node (ref "240X3") (pin "3") (pinfunction "2_3") (pintype "passive"))
      (node (ref "240X3") (pin "4") (pinfunction "2_4") (pintype "passive"))
      (node (ref "240X3") (pin "5") (pinfunction "2_5") (pintype "passive"))
      (node (ref "37X9") (pin "2") (pinfunction "2_2") (pintype "passive"))
      (node (ref "37X9") (pin "3") (pinfunction "2_3") (pintype "passive"))
      (node (ref "37X9") (pin "4") (pinfunction "2_4") (pintype "passive"))
      (node (ref "37X9") (pin "5") (pinfunction "2_5") (pintype "passive"))
      (node (ref "39X10") (pin "2") (pinfunction "2_2") (pintype "passive"))
      (node (ref "39X10") (pin "3") (pinfunction "2_3") (pintype "passive"))
      (node (ref "39X10") (pin "4") (pinfunction "2_4") (pintype "passive"))
      (node (ref "39X10") (pin "5") (pinfunction "2_5") (pintype "passive"))
      (node (ref "43X11") (pin "2") (pinfunction "2_2") (pintype "passive"))
      (node (ref "43X11") (pin "3") (pinfunction "2_3") (pintype "passive"))
      (node (ref "43X11") (pin "4") (pinfunction "2_4") (pintype "passive"))
      (node (ref "43X11") (pin "5") (pinfunction "2_5") (pintype "passive"))
      (node (ref "45X12") (pin "2") (pinfunction "2_2") (pintype "passive"))
      (node (ref "45X12") (pin "3") (pinfunction "2_3") (pintype "passive"))
      (node (ref "45X12") (pin "4") (pinfunction "2_4") (pintype "passive"))
      (node (ref "45X12") (pin "5") (pinfunction "2_5") (pintype "passive"))
      (node (ref "49X13") (pin "2") (pinfunction "2_2") (pintype "passive"))
      (node (ref "49X13") (pin "3") (pinfunction "2_3") (pintype "passive"))
      (node (ref "49X13") (pin "4") (pinfunction "2_4") (pintype "passive"))
      (node (ref "49X13") (pin "5") (pinfunction "2_5") (pintype "passive"))
      (node (ref "4X4") (pin "2") (pinfunction "2_2") (pintype "passive"))
      (node (ref "4X4") (pin "3") (pinfunction "2_3") (pintype "passive"))
      (node (ref "4X4") (pin "4") (pinfunction "2_4") (pintype "passive"))
      (node (ref "4X4") (pin "5") (pinfunction "2_5") (pintype "passive"))
      (node (ref "51X14") (pin "2") (pinfunction "2_2") (pintype "passive"))
      (node (ref "51X14") (pin "3") (pinfunction "2_3") (pintype "passive"))
      (node (ref "51X14") (pin "4") (pinfunction "2_4") (pintype "passive"))
      (node (ref "51X14") (pin "5") (pinfunction "2_5") (pintype "passive"))
      (node (ref "55X15") (pin "2") (pinfunction "2_2") (pintype "passive"))
      (node (ref "55X15") (pin "3") (pinfunction "2_3") (pintype "passive"))
      (node (ref "55X15") (pin "4") (pinfunction "2_4") (pintype "passive"))
      (node (ref "55X15") (pin "5") (pinfunction "2_5") (pintype "passive"))
      (node (ref "57X16") (pin "2") (pinfunction "2_2") (pintype "passive"))
      (node (ref "57X16") (pin "3") (pinfunction "2_3") (pintype "passive"))
      (node (ref "57X16") (pin "4") (pinfunction "2_4") (pintype "passive"))
      (node (ref "57X16") (pin "5") (pinfunction "2_5") (pintype "passive"))
      (node (ref "6X5") (pin "2") (pinfunction "2_2") (pintype "passive"))
      (node (ref "6X5") (pin "3") (pinfunction "2_3") (pintype "passive"))
      (node (ref "6X5") (pin "4") (pinfunction "2_4") (pintype "passive"))
      (node (ref "6X5") (pin "5") (pinfunction "2_5") (pintype "passive"))
      (node (ref "C1") (pin "1") (pinfunction "1_1") (pintype "passive"))
      (node (ref "C2") (pin "1") (pinfunction "1_1") (pintype "passive"))
      (node (ref "C3") (pin "1") (pinfunction "1_1") (pintype "passive"))
      (node (ref "C4") (pin "1") (pinfunction "1_1") (pintype "passive"))
      (node (ref "J1") (pin "1") (pinfunction "1_1") (pintype "bidirectional"))
      (node (ref "J10") (pin "1") (pinfunction "1_1") (pintype "bidirectional"))
      (node (ref "J11") (pin "1") (pinfunction "1_1") (pintype "bidirectional"))
      (node (ref "J12") (pin "1") (pinfunction "1_1") (pintype "bidirectional"))
      (node (ref "J13") (pin "2") (pinfunction "2_2") (pintype "passive"))
      (node (ref "J13") (pin "3") (pinfunction "3_3") (pintype "passive"))
      (node (ref "J13") (pin "4") (pinfunction "4_4") (pintype "passive"))
      (node (ref "J13") (pin "5") (pinfunction "5_5") (pintype "passive"))
      (node (ref "J13") (pin "6") (pinfunction "6_6") (pintype "passive"))
      (node (ref "J13") (pin "8") (pinfunction "8_8") (pintype "passive"))
      (node (ref "J14") (pin "1") (pinfunction "1_1") (pintype "bidirectional"))
      (node (ref "J15") (pin "1") (pinfunction "1_1") (pintype "bidirectional"))
      (node (ref "J16") (pin "1") (pinfunction "1_1") (pintype "bidirectional"))
      (node (ref "J17") (pin "1") (pinfunction "1_1") (pintype "bidirectional"))
      (node (ref "J19") (pin "1-A9") (pinfunction "MS_1-A9") (pintype "passive"))
      (node (ref "J19") (pin "1-C9") (pinfunction "MS_1-C9") (pintype "passive"))
      (node (ref "J19") (pin "2-A9") (pinfunction "MS_2-A9") (pintype "passive"))
      (node (ref "J19") (pin "2-C9") (pinfunction "MS_2-C9") (pintype "passive"))
      (node (ref "J2") (pin "1") (pinfunction "1_1") (pintype "bidirectional"))
      (node (ref "J3") (pin "1") (pinfunction "1_1") (pintype "bidirectional"))
      (node (ref "J4") (pin "1") (pinfunction "1_1") (pintype "bidirectional"))
      (node (ref "J5") (pin "1") (pinfunction "1_1") (pintype "bidirectional"))
      (node (ref "J6") (pin "1") (pinfunction "1_1") (pintype "bidirectional"))
      (node (ref "J7") (pin "1") (pinfunction "1_1") (pintype "bidirectional"))
      (node (ref "J8") (pin "1") (pinfunction "1_1") (pintype "bidirectional"))
      (node (ref "J9") (pin "1") (pinfunction "1_1") (pintype "bidirectional"))
      (node (ref "OJ1") (pin "2") (pinfunction "2_2") (pintype "bidirectional"))
      (node (ref "OJ10") (pin "2") (pinfunction "2_2") (pintype "bidirectional"))
      (node (ref "OJ11") (pin "2") (pinfunction "2_2") (pintype "bidirectional"))
      (node (ref "OJ12") (pin "2") (pinfunction "2_2") (pintype "bidirectional"))
      (node (ref "OJ13") (pin "2") (pinfunction "2_2") (pintype "bidirectional"))
      (node (ref "OJ14") (pin "2") (pinfunction "2_2") (pintype "bidirectional"))
      (node (ref "OJ15") (pin "2") (pinfunction "2_2") (pintype "bidirectional"))
      (node (ref "OJ16") (pin "2") (pinfunction "2_2") (pintype "bidirectional"))
      (node (ref "OJ17") (pin "2") (pinfunction "2_2") (pintype "bidirectional"))
      (node (ref "OJ18") (pin "2") (pinfunction "2_2") (pintype "bidirectional"))
      (node (ref "OJ19") (pin "2") (pinfunction "2_2") (pintype "bidirectional"))
      (node (ref "OJ2") (pin "2") (pinfunction "2_2") (pintype "bidirectional"))
      (node (ref "OJ20") (pin "2") (pinfunction "2_2") (pintype "bidirectional"))
      (node (ref "OJ3") (pin "2") (pinfunction "2_2") (pintype "bidirectional"))
      (node (ref "OJ4") (pin "2") (pinfunction "2_2") (pintype "bidirectional"))
      (node (ref "OJ9") (pin "2") (pinfunction "2_2") (pintype "bidirectional"))
      (node (ref "R1") (pin "P$1") (pinfunction "1_P$1") (pintype "passive"))
      (node (ref "R10") (pin "P$1") (pinfunction "1_P$1") (pintype "passive"))
      (node (ref "R11") (pin "P$1") (pinfunction "1_P$1") (pintype "passive"))
      (node (ref "R12") (pin "P$1") (pinfunction "1_P$1") (pintype "passive"))
      (node (ref "R13") (pin "P$1") (pinfunction "1_P$1") (pintype "passive"))
      (node (ref "R14") (pin "P$1") (pinfunction "1_P$1") (pintype "passive"))
      (node (ref "R15") (pin "P$1") (pinfunction "1_P$1") (pintype "passive"))
      (node (ref "R16") (pin "P$1") (pinfunction "1_P$1") (pintype "passive"))
      (node (ref "R2") (pin "P$1") (pinfunction "1_P$1") (pintype "passive"))
      (node (ref "R3") (pin "P$1") (pinfunction "1_P$1") (pintype "passive"))
      (node (ref "R4") (pin "P$1") (pinfunction "1_P$1") (pintype "passive"))
      (node (ref "R5") (pin "P$1") (pinfunction "1_P$1") (pintype "passive"))
      (node (ref "R6") (pin "P$1") (pinfunction "1_P$1") (pintype "passive"))
      (node (ref "R7") (pin "P$1") (pinfunction "1_P$1") (pintype "passive"))
      (node (ref "R8") (pin "P$1") (pinfunction "1_P$1") (pintype "passive"))
      (node (ref "R9") (pin "P$1") (pinfunction "1_P$1") (pintype "passive"))
      (node (ref "VSLUE") (pin "10") (pinfunction "GND_10") (pintype "power_in"))
      (node (ref "VSLUE2") (pin "10") (pinfunction "GND_10") (pintype "power_in"))
      (node (ref "VSLUE3") (pin "10") (pinfunction "GND_10") (pintype "power_in"))
      (node (ref "VSLUE4") (pin "10") (pinfunction "GND_10") (pintype "power_in"))
      (node (ref "X13") (pin "2") (pinfunction "S_2") (pintype "passive"))
      (node (ref "X13") (pin "24") (pinfunction "S_24") (pintype "passive"))
      (node (ref "X18") (pin "1") (pinfunction "S_1") (pintype "passive"))
      (node (ref "X18") (pin "23") (pinfunction "S_23") (pintype "passive"))
    )
    (net (code "5") (name "/IO4") (class "Default")
      (node (ref "4X4") (pin "1") (pinfunction "1_1") (pintype "passive"))
      (node (ref "J7") (pin "2") (pinfunction "2_2") (pintype "bidirectional"))
      (node (ref "R7") (pin "P$2") (pinfunction "2_P$2") (pintype "passive"))
      (node (ref "X18") (pin "10") (pinfunction "S_10") (pintype "passive"))
    )
    (net (code "6") (name "/IO6") (class "Default")
      (node (ref "6X5") (pin "1") (pinfunction "1_1") (pintype "passive"))
      (node (ref "J8") (pin "2") (pinfunction "2_2") (pintype "bidirectional"))
      (node (ref "R8") (pin "P$2") (pinfunction "2_P$2") (pintype "passive"))
      (node (ref "X18") (pin "12") (pinfunction "S_12") (pintype "passive"))
    )
    (net (code "7") (name "/IO13") (class "Default")
      (node (ref "13X6") (pin "1") (pinfunction "1_1") (pintype "passive"))
      (node (ref "J9") (pin "2") (pinfunction "2_2") (pintype "bidirectional"))
      (node (ref "R9") (pin "P$2") (pinfunction "2_P$2") (pintype "passive"))
      (node (ref "X18") (pin "14") (pinfunction "S_14") (pintype "passive"))
    )
    (net (code "8") (name "/IO19") (class "Default")
      (node (ref "19X7") (pin "1") (pinfunction "1_1") (pintype "passive"))
      (node (ref "J10") (pin "2") (pinfunction "2_2") (pintype "bidirectional"))
      (node (ref "R10") (pin "P$2") (pinfunction "2_P$2") (pintype "passive"))
      (node (ref "X18") (pin "16") (pinfunction "S_16") (pintype "passive"))
    )
    (net (code "9") (name "/IO21") (class "Default")
      (node (ref "21X8") (pin "1") (pinfunction "1_1") (pintype "passive"))
      (node (ref "J11") (pin "2") (pinfunction "2_2") (pintype "bidirectional"))
      (node (ref "R11") (pin "P$2") (pinfunction "2_P$2") (pintype "passive"))
      (node (ref "X18") (pin "18") (pinfunction "S_18") (pintype "passive"))
    )
    (net (code "10") (name "/IO37") (class "Default")
      (node (ref "37X9") (pin "1") (pinfunction "1_1") (pintype "passive"))
      (node (ref "J12") (pin "2") (pinfunction "2_2") (pintype "bidirectional"))
      (node (ref "R12") (pin "P$2") (pinfunction "2_P$2") (pintype "passive"))
      (node (ref "X18") (pin "20") (pinfunction "S_20") (pintype "passive"))
    )
    (net (code "11") (name "/IO39") (class "Default")
      (node (ref "39X10") (pin "1") (pinfunction "1_1") (pintype "passive"))
      (node (ref "J14") (pin "2") (pinfunction "2_2") (pintype "bidirectional"))
      (node (ref "R13") (pin "P$2") (pinfunction "2_P$2") (pintype "passive"))
      (node (ref "X18") (pin "22") (pinfunction "S_22") (pintype "passive"))
    )
    (net (code "12") (name "/IO43") (class "Default")
      (node (ref "43X11") (pin "1") (pinfunction "1_1") (pintype "passive"))
      (node (ref "J15") (pin "2") (pinfunction "2_2") (pintype "bidirectional"))
      (node (ref "R14") (pin "P$2") (pinfunction "2_P$2") (pintype "passive"))
      (node (ref "X18") (pin "26") (pinfunction "S_26") (pintype "passive"))
    )
    (net (code "13") (name "/IO45") (class "Default")
      (node (ref "45X12") (pin "1") (pinfunction "1_1") (pintype "passive"))
      (node (ref "J16") (pin "2") (pinfunction "2_2") (pintype "bidirectional"))
      (node (ref "R15") (pin "P$2") (pinfunction "2_P$2") (pintype "passive"))
      (node (ref "X18") (pin "28") (pinfunction "S_28") (pintype "passive"))
    )
    (net (code "14") (name "/IO49") (class "Default")
      (node (ref "49X13") (pin "1") (pinfunction "1_1") (pintype "passive"))
      (node (ref "J17") (pin "2") (pinfunction "2_2") (pintype "bidirectional"))
      (node (ref "R16") (pin "P$2") (pinfunction "2_P$2") (pintype "passive"))
      (node (ref "X17") (pin "2") (pinfunction "S_2") (pintype "passive"))
    )
    (net (code "15") (name "/IO51") (class "Default")
      (node (ref "51X14") (pin "1") (pinfunction "1_1") (pintype "passive"))
      (node (ref "J4") (pin "2") (pinfunction "2_2") (pintype "bidirectional"))
      (node (ref "R4") (pin "P$2") (pinfunction "2_P$2") (pintype "passive"))
      (node (ref "X17") (pin "4") (pinfunction "S_4") (pintype "passive"))
    )
    (net (code "16") (name "/IO55") (class "Default")
      (node (ref "55X15") (pin "1") (pinfunction "1_1") (pintype "passive"))
      (node (ref "J5") (pin "2") (pinfunction "2_2") (pintype "bidirectional"))
      (node (ref "R5") (pin "P$2") (pinfunction "2_P$2") (pintype "passive"))
      (node (ref "X17") (pin "6") (pinfunction "S_6") (pintype "passive"))
    )
    (net (code "17") (name "/IO57") (class "Default")
      (node (ref "57X16") (pin "1") (pinfunction "1_1") (pintype "passive"))
      (node (ref "J6") (pin "2") (pinfunction "2_2") (pintype "bidirectional"))
      (node (ref "R6") (pin "P$2") (pinfunction "2_P$2") (pintype "passive"))
      (node (ref "X17") (pin "8") (pinfunction "S_8") (pintype "passive"))
    )
    (net (code "18") (name "/IO145_IN4") (class "Default")
      (node (ref "VSLUE4") (pin "15") (pinfunction "2A3_15") (pintype "input"))
      (node (ref "VSLUE4") (pin "17") (pinfunction "2A4_17") (pintype "input"))
      (node (ref "X13") (pin "28") (pinfunction "S_28") (pintype "passive"))
    )
    (net (code "19") (name "/IO147_IN3") (class "Default")
      (node (ref "VSLUE4") (pin "11") (pinfunction "2A1_11") (pintype "input"))
      (node (ref "VSLUE4") (pin "13") (pinfunction "2A2_13") (pintype "input"))
      (node (ref "X13") (pin "26") (pinfunction "S_26") (pintype "passive"))
    )
    (net (code "20") (name "/IO159_IN2") (class "Default")
      (node (ref "VSLUE4") (pin "6") (pinfunction "1A3_6") (pintype "input"))
      (node (ref "VSLUE4") (pin "8") (pinfunction "1A4_8") (pintype "input"))
      (node (ref "X13") (pin "22") (pinfunction "S_22") (pintype "passive"))
    )
    (net (code "21") (name "/IO161_IN1") (class "Default")
      (node (ref "VSLUE4") (pin "2") (pinfunction "1A1_2") (pintype "input"))
      (node (ref "VSLUE4") (pin "4") (pinfunction "1A2_4") (pintype "input"))
      (node (ref "X13") (pin "20") (pinfunction "S_20") (pintype "passive"))
    )
    (net (code "22") (name "/IO164_IN4") (class "Default")
      (node (ref "VSLUE3") (pin "15") (pinfunction "2A3_15") (pintype "input"))
      (node (ref "VSLUE3") (pin "17") (pinfunction "2A4_17") (pintype "input"))
      (node (ref "X13") (pin "18") (pinfunction "S_18") (pintype "passive"))
    )
    (net (code "23") (name "/IO167_IN3") (class "Default")
      (node (ref "VSLUE3") (pin "11") (pinfunction "2A1_11") (pintype "input"))
      (node (ref "VSLUE3") (pin "13") (pinfunction "2A2_13") (pintype "input"))
      (node (ref "X13") (pin "16") (pinfunction "S_16") (pintype "passive"))
    )
    (net (code "24") (name "/IO169_IN2") (class "Default")
      (node (ref "VSLUE3") (pin "6") (pinfunction "1A3_6") (pintype "input"))
      (node (ref "VSLUE3") (pin "8") (pinfunction "1A4_8") (pintype "input"))
      (node (ref "X13") (pin "14") (pinfunction "S_14") (pintype "passive"))
    )
    (net (code "25") (name "/IO173_IN1") (class "Default")
      (node (ref "VSLUE3") (pin "2") (pinfunction "1A1_2") (pintype "input"))
      (node (ref "VSLUE3") (pin "4") (pinfunction "1A2_4") (pintype "input"))
      (node (ref "X13") (pin "12") (pinfunction "S_12") (pintype "passive"))
    )
    (net (code "26") (name "/IO174_IN1") (class "Default")
      (node (ref "VSLUE") (pin "2") (pinfunction "1A1_2") (pintype "input"))
      (node (ref "VSLUE") (pin "4") (pinfunction "1A2_4") (pintype "input"))
      (node (ref "X13") (pin "9") (pinfunction "S_9") (pintype "passive"))
    )
    (net (code "27") (name "/IO175_IN1") (class "Default")
      (node (ref "VSLUE2") (pin "2") (pinfunction "1A1_2") (pintype "input"))
      (node (ref "VSLUE2") (pin "4") (pinfunction "1A2_4") (pintype "input"))
      (node (ref "X13") (pin "10") (pinfunction "S_10") (pintype "passive"))
    )
    (net (code "28") (name "/IO176_IN2") (class "Default")
      (node (ref "VSLUE") (pin "6") (pinfunction "1A3_6") (pintype "input"))
      (node (ref "VSLUE") (pin "8") (pinfunction "1A4_8") (pintype "input"))
      (node (ref "X13") (pin "7") (pinfunction "S_7") (pintype "passive"))
    )
    (net (code "29") (name "/IO177_IN2") (class "Default")
      (node (ref "VSLUE2") (pin "6") (pinfunction "1A3_6") (pintype "input"))
      (node (ref "VSLUE2") (pin "8") (pinfunction "1A4_8") (pintype "input"))
      (node (ref "X13") (pin "8") (pinfunction "S_8") (pintype "passive"))
    )
    (net (code "30") (name "/IO181_IN3") (class "Default")
      (node (ref "VSLUE") (pin "11") (pinfunction "2A1_11") (pintype "input"))
      (node (ref "VSLUE") (pin "13") (pinfunction "2A2_13") (pintype "input"))
      (node (ref "X13") (pin "5") (pinfunction "S_5") (pintype "passive"))
    )
    (net (code "31") (name "/IO182_IN3") (class "Default")
      (node (ref "VSLUE2") (pin "11") (pinfunction "2A1_11") (pintype "input"))
      (node (ref "VSLUE2") (pin "13") (pinfunction "2A2_13") (pintype "input"))
      (node (ref "X13") (pin "6") (pinfunction "S_6") (pintype "passive"))
    )
    (net (code "32") (name "/IO183_IN4") (class "Default")
      (node (ref "VSLUE") (pin "15") (pinfunction "2A3_15") (pintype "input"))
      (node (ref "VSLUE") (pin "17") (pinfunction "2A4_17") (pintype "input"))
      (node (ref "X13") (pin "3") (pinfunction "S_3") (pintype "passive"))
    )
    (net (code "33") (name "/IO184_IN4") (class "Default")
      (node (ref "VSLUE2") (pin "15") (pinfunction "2A3_15") (pintype "input"))
      (node (ref "VSLUE2") (pin "17") (pinfunction "2A4_17") (pintype "input"))
      (node (ref "X13") (pin "4") (pinfunction "S_4") (pintype "passive"))
    )
    (net (code "34") (name "/IO185") (class "Default")
      (node (ref "J18") (pin "8") (pinfunction "8_8") (pintype "passive"))
      (node (ref "X15") (pin "16") (pinfunction "S_16") (pintype "passive"))
    )
    (net (code "35") (name "/IO187") (class "Default")
      (node (ref "J18") (pin "7") (pinfunction "7_7") (pintype "passive"))
      (node (ref "X15") (pin "14") (pinfunction "S_14") (pintype "passive"))
    )
    (net (code "36") (name "/IO189") (class "Default")
      (node (ref "J18") (pin "6") (pinfunction "6_6") (pintype "passive"))
      (node (ref "X15") (pin "12") (pinfunction "S_12") (pintype "passive"))
    )
    (net (code "37") (name "/IO195") (class "Default")
      (node (ref "J18") (pin "5") (pinfunction "5_5") (pintype "passive"))
      (node (ref "X15") (pin "10") (pinfunction "S_10") (pintype "passive"))
    )
    (net (code "38") (name "/IO197") (class "Default")
      (node (ref "J18") (pin "4") (pinfunction "4_4") (pintype "passive"))
      (node (ref "X15") (pin "8") (pinfunction "S_8") (pintype "passive"))
    )
    (net (code "39") (name "/IO199") (class "Default")
      (node (ref "J18") (pin "3") (pinfunction "3_3") (pintype "passive"))
      (node (ref "X15") (pin "6") (pinfunction "S_6") (pintype "passive"))
    )
    (net (code "40") (name "/IO201") (class "Default")
      (node (ref "J18") (pin "2") (pinfunction "2_2") (pintype "passive"))
      (node (ref "X15") (pin "4") (pinfunction "S_4") (pintype "passive"))
    )
    (net (code "41") (name "/IO203") (class "Default")
      (node (ref "J18") (pin "1") (pinfunction "1_1") (pintype "passive"))
      (node (ref "X15") (pin "2") (pinfunction "S_2") (pintype "passive"))
    )
    (net (code "42") (name "/IO236") (class "Default")
      (node (ref "236X1") (pin "1") (pinfunction "1_1") (pintype "passive"))
      (node (ref "J1") (pin "2") (pinfunction "2_2") (pintype "bidirectional"))
      (node (ref "R1") (pin "P$2") (pinfunction "2_P$2") (pintype "passive"))
      (node (ref "X18") (pin "4") (pinfunction "S_4") (pintype "passive"))
    )
    (net (code "43") (name "/IO238") (class "Default")
      (node (ref "238X2") (pin "1") (pinfunction "1_1") (pintype "passive"))
      (node (ref "J2") (pin "2") (pinfunction "2_2") (pintype "bidirectional"))
      (node (ref "R2") (pin "P$2") (pinfunction "2_P$2") (pintype "passive"))
      (node (ref "X18") (pin "6") (pinfunction "S_6") (pintype "passive"))
    )
    (net (code "44") (name "/IO240") (class "Default")
      (node (ref "240X3") (pin "1") (pinfunction "1_1") (pintype "passive"))
      (node (ref "J3") (pin "2") (pinfunction "2_2") (pintype "bidirectional"))
      (node (ref "R3") (pin "P$2") (pinfunction "2_P$2") (pintype "passive"))
      (node (ref "X18") (pin "8") (pinfunction "S_8") (pintype "passive"))
    )
    (net (code "45") (name "/OUT1") (class "Default")
      (node (ref "174OUT1") (pin "1") (pinfunction "1_1") (pintype "passive"))
      (node (ref "OJ1") (pin "1") (pinfunction "1_1") (pintype "bidirectional"))
      (node (ref "VSLUE") (pin "16") (pinfunction "1Y2_16") (pintype "output"))
      (node (ref "VSLUE") (pin "18") (pinfunction "1Y1_18") (pintype "output"))
    )
    (net (code "46") (name "/OUT2") (class "Default")
      (node (ref "176OUT2") (pin "1") (pinfunction "1_1") (pintype "passive"))
      (node (ref "OJ2") (pin "1") (pinfunction "1_1") (pintype "bidirectional"))
      (node (ref "VSLUE") (pin "12") (pinfunction "1Y4_12") (pintype "output"))
      (node (ref "VSLUE") (pin "14") (pinfunction "1Y3_14") (pintype "output"))
    )
    (net (code "47") (name "/OUT3") (class "Default")
      (node (ref "181OUT3") (pin "1") (pinfunction "1_1") (pintype "passive"))
      (node (ref "OJ3") (pin "1") (pinfunction "1_1") (pintype "bidirectional"))
      (node (ref "VSLUE") (pin "7") (pinfunction "2Y2_7") (pintype "output"))
      (node (ref "VSLUE") (pin "9") (pinfunction "2Y1_9") (pintype "output"))
    )
    (net (code "48") (name "/OUT4") (class "Default")
      (node (ref "183OUT4") (pin "1") (pinfunction "1_1") (pintype "passive"))
      (node (ref "OJ4") (pin "1") (pinfunction "1_1") (pintype "bidirectional"))
      (node (ref "VSLUE") (pin "3") (pinfunction "2Y4_3") (pintype "output"))
      (node (ref "VSLUE") (pin "5") (pinfunction "2Y3_5") (pintype "output"))
    )
    (net (code "49") (name "/OUT5") (class "Default")
      (node (ref "175OUT5") (pin "1") (pinfunction "1_1") (pintype "passive"))
      (node (ref "OJ12") (pin "1") (pinfunction "1_1") (pintype "bidirectional"))
      (node (ref "VSLUE2") (pin "16") (pinfunction "1Y2_16") (pintype "output"))
      (node (ref "VSLUE2") (pin "18") (pinfunction "1Y1_18") (pintype "output"))
    )
    (net (code "50") (name "/OUT6") (class "Default")
      (node (ref "177OUT6") (pin "1") (pinfunction "1_1") (pintype "passive"))
      (node (ref "OJ11") (pin "1") (pinfunction "1_1") (pintype "bidirectional"))
      (node (ref "VSLUE2") (pin "12") (pinfunction "1Y4_12") (pintype "output"))
      (node (ref "VSLUE2") (pin "14") (pinfunction "1Y3_14") (pintype "output"))
    )
    (net (code "51") (name "/OUT7") (class "Default")
      (node (ref "182OUT7") (pin "1") (pinfunction "1_1") (pintype "passive"))
      (node (ref "OJ10") (pin "1") (pinfunction "1_1") (pintype "bidirectional"))
      (node (ref "VSLUE2") (pin "7") (pinfunction "2Y2_7") (pintype "output"))
      (node (ref "VSLUE2") (pin "9") (pinfunction "2Y1_9") (pintype "output"))
    )
    (net (code "52") (name "/OUT8") (class "Default")
      (node (ref "184OUT8") (pin "1") (pinfunction "1_1") (pintype "passive"))
      (node (ref "OJ9") (pin "1") (pinfunction "1_1") (pintype "bidirectional"))
      (node (ref "VSLUE2") (pin "3") (pinfunction "2Y4_3") (pintype "output"))
      (node (ref "VSLUE2") (pin "5") (pinfunction "2Y3_5") (pintype "output"))
    )
    (net (code "53") (name "/OUT9") (class "Default")
      (node (ref "173OUT9") (pin "1") (pinfunction "1_1") (pintype "passive"))
      (node (ref "OJ16") (pin "1") (pinfunction "1_1") (pintype "bidirectional"))
      (node (ref "VSLUE3") (pin "16") (pinfunction "1Y2_16") (pintype "output"))
      (node (ref "VSLUE3") (pin "18") (pinfunction "1Y1_18") (pintype "output"))
    )
    (net (code "54") (name "/OUT10") (class "Default")
      (node (ref "169OUT10") (pin "1") (pinfunction "1_1") (pintype "passive"))
      (node (ref "OJ15") (pin "1") (pinfunction "1_1") (pintype "bidirectional"))
      (node (ref "VSLUE3") (pin "12") (pinfunction "1Y4_12") (pintype "output"))
      (node (ref "VSLUE3") (pin "14") (pinfunction "1Y3_14") (pintype "output"))
    )
    (net (code "55") (name "/OUT11") (class "Default")
      (node (ref "167OUT11") (pin "1") (pinfunction "1_1") (pintype "passive"))
      (node (ref "OJ14") (pin "1") (pinfunction "1_1") (pintype "bidirectional"))
      (node (ref "VSLUE3") (pin "7") (pinfunction "2Y2_7") (pintype "output"))
      (node (ref "VSLUE3") (pin "9") (pinfunction "2Y1_9") (pintype "output"))
    )
    (net (code "56") (name "/OUT12") (class "Default")
      (node (ref "164OUT12") (pin "1") (pinfunction "1_1") (pintype "passive"))
      (node (ref "OJ13") (pin "1") (pinfunction "1_1") (pintype "bidirectional"))
      (node (ref "VSLUE3") (pin "3") (pinfunction "2Y4_3") (pintype "output"))
      (node (ref "VSLUE3") (pin "5") (pinfunction "2Y3_5") (pintype "output"))
    )
    (net (code "57") (name "/OUT13") (class "Default")
      (node (ref "161OUT13") (pin "1") (pinfunction "1_1") (pintype "passive"))
      (node (ref "OJ20") (pin "1") (pinfunction "1_1") (pintype "bidirectional"))
      (node (ref "VSLUE4") (pin "16") (pinfunction "1Y2_16") (pintype "output"))
      (node (ref "VSLUE4") (pin "18") (pinfunction "1Y1_18") (pintype "output"))
    )
    (net (code "58") (name "/OUT14") (class "Default")
      (node (ref "159OUT14") (pin "1") (pinfunction "1_1") (pintype "passive"))
      (node (ref "OJ19") (pin "1") (pinfunction "1_1") (pintype "bidirectional"))
      (node (ref "VSLUE4") (pin "12") (pinfunction "1Y4_12") (pintype "output"))
      (node (ref "VSLUE4") (pin "14") (pinfunction "1Y3_14") (pintype "output"))
    )
    (net (code "59") (name "/OUT15") (class "Default")
      (node (ref "147OUT15") (pin "1") (pinfunction "1_1") (pintype "passive"))
      (node (ref "OJ18") (pin "1") (pinfunction "1_1") (pintype "bidirectional"))
      (node (ref "VSLUE4") (pin "7") (pinfunction "2Y2_7") (pintype "output"))
      (node (ref "VSLUE4") (pin "9") (pinfunction "2Y1_9") (pintype "output"))
    )
    (net (code "60") (name "/OUT16") (class "Default")
      (node (ref "145OUT16") (pin "1") (pinfunction "1_1") (pintype "passive"))
      (node (ref "OJ17") (pin "1") (pinfunction "1_1") (pintype "bidirectional"))
      (node (ref "VSLUE4") (pin "3") (pinfunction "2Y4_3") (pintype "output"))
      (node (ref "VSLUE4") (pin "5") (pinfunction "2Y3_5") (pintype "output"))
    )
    (net (code "61") (name "unconnected-(J19A-MSV-Pad1-A1)") (class "Default")
      (node (ref "J19") (pin "1-A1") (pinfunction "MSV_1-A1") (pintype "passive"))
    )
    (net (code "62") (name "unconnected-(J19AA-MS-Pad1-A4)") (class "Default")
      (node (ref "J19") (pin "1-A4") (pinfunction "MS_1-A4") (pintype "passive"))
    )
    (net (code "63") (name "unconnected-(J19AB-MS-Pad1-A5)") (class "Default")
      (node (ref "J19") (pin "1-A5") (pinfunction "MS_1-A5") (pintype "passive"))
    )
    (net (code "64") (name "unconnected-(J19AC-MS-Pad1-A6)") (class "Default")
      (node (ref "J19") (pin "1-A6") (pinfunction "MS_1-A6") (pintype "passive"))
    )
    (net (code "65") (name "unconnected-(J19AD-MS-Pad1-A7)") (class "Default")
      (node (ref "J19") (pin "1-A7") (pinfunction "MS_1-A7") (pintype "passive"))
    )
    (net (code "66") (name "unconnected-(J19AE-MS-Pad1-A8)") (class "Default")
      (node (ref "J19") (pin "1-A8") (pinfunction "MS_1-A8") (pintype "passive"))
    )
    (net (code "67") (name "unconnected-(J19AG-MSV-Pad1-C1)") (class "Default")
      (node (ref "J19") (pin "1-C1") (pinfunction "MSV_1-C1") (pintype "passive"))
    )
    (net (code "68") (name "unconnected-(J19AH-MS-Pad1-C10)") (class "Default")
      (node (ref "J19") (pin "1-C10") (pinfunction "MS_1-C10") (pintype "passive"))
    )
    (net (code "69") (name "unconnected-(J19AI-MS-Pad1-C11)") (class "Default")
      (node (ref "J19") (pin "1-C11") (pinfunction "MS_1-C11") (pintype "passive"))
    )
    (net (code "70") (name "unconnected-(J19AJ-MS-Pad1-C12)") (class "Default")
      (node (ref "J19") (pin "1-C12") (pinfunction "MS_1-C12") (pintype "passive"))
    )
    (net (code "71") (name "unconnected-(J19AK-MS-Pad1-C13)") (class "Default")
      (node (ref "J19") (pin "1-C13") (pinfunction "MS_1-C13") (pintype "passive"))
    )
    (net (code "72") (name "unconnected-(J19AL-MS-Pad1-C14)") (class "Default")
      (node (ref "J19") (pin "1-C14") (pinfunction "MS_1-C14") (pintype "passive"))
    )
    (net (code "73") (name "unconnected-(J19AM-MS-Pad1-C15)") (class "Default")
      (node (ref "J19") (pin "1-C15") (pinfunction "MS_1-C15") (pintype "passive"))
    )
    (net (code "74") (name "unconnected-(J19AN-MS-Pad1-C16)") (class "Default")
      (node (ref "J19") (pin "1-C16") (pinfunction "MS_1-C16") (pintype "passive"))
    )
    (net (code "75") (name "unconnected-(J19AO-MS-Pad1-C17)") (class "Default")
      (node (ref "J19") (pin "1-C17") (pinfunction "MS_1-C17") (pintype "passive"))
    )
    (net (code "76") (name "unconnected-(J19AP-MS-Pad1-C18)") (class "Default")
      (node (ref "J19") (pin "1-C18") (pinfunction "MS_1-C18") (pintype "passive"))
    )
    (net (code "77") (name "unconnected-(J19AQ-MS-Pad1-C19)") (class "Default")
      (node (ref "J19") (pin "1-C19") (pinfunction "MS_1-C19") (pintype "passive"))
    )
    (net (code "78") (name "unconnected-(J19AR-MS-Pad1-C2)") (class "Default")
      (node (ref "J19") (pin "1-C2") (pinfunction "MS_1-C2") (pintype "passive"))
    )
    (net (code "79") (name "unconnected-(J19AS-MS-Pad1-C20)") (class "Default")
      (node (ref "J19") (pin "1-C20") (pinfunction "MS_1-C20") (pintype "passive"))
    )
    (net (code "80") (name "unconnected-(J19AT-MS-Pad1-C21)") (class "Default")
      (node (ref "J19") (pin "1-C21") (pinfunction "MS_1-C21") (pintype "passive"))
    )
    (net (code "81") (name "unconnected-(J19AU-MS-Pad1-C22)") (class "Default")
      (node (ref "J19") (pin "1-C22") (pinfunction "MS_1-C22") (pintype "passive"))
    )
    (net (code "82") (name "unconnected-(J19AV-MS-Pad1-C23)") (class "Default")
      (node (ref "J19") (pin "1-C23") (pinfunction "MS_1-C23") (pintype "passive"))
    )
    (net (code "83") (name "unconnected-(J19AW-MS-Pad1-C24)") (class "Default")
      (node (ref "J19") (pin "1-C24") (pinfunction "MS_1-C24") (pintype "passive"))
    )
    (net (code "84") (name "unconnected-(J19AX-MS-Pad1-C25)") (class "Default")
      (node (ref "J19") (pin "1-C25") (pinfunction "MS_1-C25") (pintype "passive"))
    )
    (net (code "85") (name "unconnected-(J19AY-MS-Pad1-C26)") (class "Default")
      (node (ref "J19") (pin "1-C26") (pinfunction "MS_1-C26") (pintype "passive"))
    )
    (net (code "86") (name "unconnected-(J19AZ-MS-Pad1-C27)") (class "Default")
      (node (ref "J19") (pin "1-C27") (pinfunction "MS_1-C27") (pintype "passive"))
    )
    (net (code "87") (name "unconnected-(J19B-MS-Pad1-A10)") (class "Default")
      (node (ref "J19") (pin "1-A10") (pinfunction "MS_1-A10") (pintype "passive"))
    )
    (net (code "88") (name "unconnected-(J19BA-MS-Pad1-C28)") (class "Default")
      (node (ref "J19") (pin "1-C28") (pinfunction "MS_1-C28") (pintype "passive"))
    )
    (net (code "89") (name "unconnected-(J19BB-MS-Pad1-C29)") (class "Default")
      (node (ref "J19") (pin "1-C29") (pinfunction "MS_1-C29") (pintype "passive"))
    )
    (net (code "90") (name "unconnected-(J19BC-MS-Pad1-C3)") (class "Default")
      (node (ref "J19") (pin "1-C3") (pinfunction "MS_1-C3") (pintype "passive"))
    )
    (net (code "91") (name "unconnected-(J19BD-MS-Pad1-C30)") (class "Default")
      (node (ref "J19") (pin "1-C30") (pinfunction "MS_1-C30") (pintype "passive"))
    )
    (net (code "92") (name "unconnected-(J19BE-MS-Pad1-C31)") (class "Default")
      (node (ref "J19") (pin "1-C31") (pinfunction "MS_1-C31") (pintype "passive"))
    )
    (net (code "93") (name "unconnected-(J19BG-MS-Pad1-C4)") (class "Default")
      (node (ref "J19") (pin "1-C4") (pinfunction "MS_1-C4") (pintype "passive"))
    )
    (net (code "94") (name "unconnected-(J19BH-MS-Pad1-C5)") (class "Default")
      (node (ref "J19") (pin "1-C5") (pinfunction "MS_1-C5") (pintype "passive"))
    )
    (net (code "95") (name "unconnected-(J19BI-MS-Pad1-C6)") (class "Default")
      (node (ref "J19") (pin "1-C6") (pinfunction "MS_1-C6") (pintype "passive"))
    )
    (net (code "96") (name "unconnected-(J19BJ-MS-Pad1-C7)") (class "Default")
      (node (ref "J19") (pin "1-C7") (pinfunction "MS_1-C7") (pintype "passive"))
    )
    (net (code "97") (name "unconnected-(J19BK-MS-Pad1-C8)") (class "Default")
      (node (ref "J19") (pin "1-C8") (pinfunction "MS_1-C8") (pintype "passive"))
    )
    (net (code "98") (name "unconnected-(J19BM-MSV-Pad2-A1)") (class "Default")
      (node (ref "J19") (pin "2-A1") (pinfunction "MSV_2-A1") (pintype "passive"))
    )
    (net (code "99") (name "unconnected-(J19BN-MS-Pad2-A10)") (class "Default")
      (node (ref "J19") (pin "2-A10") (pinfunction "MS_2-A10") (pintype "passive"))
    )
    (net (code "100") (name "unconnected-(J19BO-MS-Pad2-A11)") (class "Default")
      (node (ref "J19") (pin "2-A11") (pinfunction "MS_2-A11") (pintype "passive"))
    )
    (net (code "101") (name "unconnected-(J19BP-MS-Pad2-A12)") (class "Default")
      (node (ref "J19") (pin "2-A12") (pinfunction "MS_2-A12") (pintype "passive"))
    )
    (net (code "102") (name "unconnected-(J19BQ-MS-Pad2-A13)") (class "Default")
      (node (ref "J19") (pin "2-A13") (pinfunction "MS_2-A13") (pintype "passive"))
    )
    (net (code "103") (name "unconnected-(J19BR-MS-Pad2-A14)") (class "Default")
      (node (ref "J19") (pin "2-A14") (pinfunction "MS_2-A14") (pintype "passive"))
    )
    (net (code "104") (name "unconnected-(J19BS-MS-Pad2-A15)") (class "Default")
      (node (ref "J19") (pin "2-A15") (pinfunction "MS_2-A15") (pintype "passive"))
    )
    (net (code "105") (name "unconnected-(J19BT-MS-Pad2-A16)") (class "Default")
      (node (ref "J19") (pin "2-A16") (pinfunction "MS_2-A16") (pintype "passive"))
    )
    (net (code "106") (name "unconnected-(J19BU-MS-Pad2-A17)") (class "Default")
      (node (ref "J19") (pin "2-A17") (pinfunction "MS_2-A17") (pintype "passive"))
    )
    (net (code "107") (name "unconnected-(J19BV-MS-Pad2-A18)") (class "Default")
      (node (ref "J19") (pin "2-A18") (pinfunction "MS_2-A18") (pintype "passive"))
    )
    (net (code "108") (name "unconnected-(J19BW-MS-Pad2-A19)") (class "Default")
      (node (ref "J19") (pin "2-A19") (pinfunction "MS_2-A19") (pintype "passive"))
    )
    (net (code "109") (name "unconnected-(J19BX-MS-Pad2-A2)") (class "Default")
      (node (ref "J19") (pin "2-A2") (pinfunction "MS_2-A2") (pintype "passive"))
    )
    (net (code "110") (name "unconnected-(J19BY-MS-Pad2-A20)") (class "Default")
      (node (ref "J19") (pin "2-A20") (pinfunction "MS_2-A20") (pintype "passive"))
    )
    (net (code "111") (name "unconnected-(J19BZ-MS-Pad2-A21)") (class "Default")
      (node (ref "J19") (pin "2-A21") (pinfunction "MS_2-A21") (pintype "passive"))
    )
    (net (code "112") (name "unconnected-(J19C-MS-Pad1-A11)") (class "Default")
      (node (ref "J19") (pin "1-A11") (pinfunction "MS_1-A11") (pintype "passive"))
    )
    (net (code "113") (name "unconnected-(J19CA-MS-Pad2-A22)") (class "Default")
      (node (ref "J19") (pin "2-A22") (pinfunction "MS_2-A22") (pintype "passive"))
    )
    (net (code "114") (name "unconnected-(J19CB-MS-Pad2-A23)") (class "Default")
      (node (ref "J19") (pin "2-A23") (pinfunction "MS_2-A23") (pintype "passive"))
    )
    (net (code "115") (name "unconnected-(J19CC-MS-Pad2-A24)") (class "Default")
      (node (ref "J19") (pin "2-A24") (pinfunction "MS_2-A24") (pintype "passive"))
    )
    (net (code "116") (name "unconnected-(J19CD-MS-Pad2-A25)") (class "Default")
      (node (ref "J19") (pin "2-A25") (pinfunction "MS_2-A25") (pintype "passive"))
    )
    (net (code "117") (name "unconnected-(J19CE-MS-Pad2-A26)") (class "Default")
      (node (ref "J19") (pin "2-A26") (pinfunction "MS_2-A26") (pintype "passive"))
    )
    (net (code "118") (name "unconnected-(J19CF-MS-Pad2-A27)") (class "Default")
      (node (ref "J19") (pin "2-A27") (pinfunction "MS_2-A27") (pintype "passive"))
    )
    (net (code "119") (name "unconnected-(J19CG-MS-Pad2-A28)") (class "Default")
      (node (ref "J19") (pin "2-A28") (pinfunction "MS_2-A28") (pintype "passive"))
    )
    (net (code "120") (name "unconnected-(J19CH-MS-Pad2-A29)") (class "Default")
      (node (ref "J19") (pin "2-A29") (pinfunction "MS_2-A29") (pintype "passive"))
    )
    (net (code "121") (name "unconnected-(J19CI-MS-Pad2-A3)") (class "Default")
      (node (ref "J19") (pin "2-A3") (pinfunction "MS_2-A3") (pintype "passive"))
    )
    (net (code "122") (name "unconnected-(J19CJ-MS-Pad2-A30)") (class "Default")
      (node (ref "J19") (pin "2-A30") (pinfunction "MS_2-A30") (pintype "passive"))
    )
    (net (code "123") (name "unconnected-(J19CK-MS-Pad2-A31)") (class "Default")
      (node (ref "J19") (pin "2-A31") (pinfunction "MS_2-A31") (pintype "passive"))
    )
    (net (code "124") (name "unconnected-(J19CM-MS-Pad2-A4)") (class "Default")
      (node (ref "J19") (pin "2-A4") (pinfunction "MS_2-A4") (pintype "passive"))
    )
    (net (code "125") (name "unconnected-(J19CN-MS-Pad2-A5)") (class "Default")
      (node (ref "J19") (pin "2-A5") (pinfunction "MS_2-A5") (pintype "passive"))
    )
    (net (code "126") (name "unconnected-(J19CO-MS-Pad2-A6)") (class "Default")
      (node (ref "J19") (pin "2-A6") (pinfunction "MS_2-A6") (pintype "passive"))
    )
    (net (code "127") (name "unconnected-(J19CP-MS-Pad2-A7)") (class "Default")
      (node (ref "J19") (pin "2-A7") (pinfunction "MS_2-A7") (pintype "passive"))
    )
    (net (code "128") (name "unconnected-(J19CQ-MS-Pad2-A8)") (class "Default")
      (node (ref "J19") (pin "2-A8") (pinfunction "MS_2-A8") (pintype "passive"))
    )
    (net (code "129") (name "unconnected-(J19CS-MSV-Pad2-C1)") (class "Default")
      (node (ref "J19") (pin "2-C1") (pinfunction "MSV_2-C1") (pintype "passive"))
    )
    (net (code "130") (name "unconnected-(J19CT-MS-Pad2-C10)") (class "Default")
      (node (ref "J19") (pin "2-C10") (pinfunction "MS_2-C10") (pintype "passive"))
    )
    (net (code "131") (name "unconnected-(J19CU-MS-Pad2-C11)") (class "Default")
      (node (ref "J19") (pin "2-C11") (pinfunction "MS_2-C11") (pintype "passive"))
    )
    (net (code "132") (name "unconnected-(J19CV-MS-Pad2-C12)") (class "Default")
      (node (ref "J19") (pin "2-C12") (pinfunction "MS_2-C12") (pintype "passive"))
    )
    (net (code "133") (name "unconnected-(J19CW-MS-Pad2-C13)") (class "Default")
      (node (ref "J19") (pin "2-C13") (pinfunction "MS_2-C13") (pintype "passive"))
    )
    (net (code "134") (name "unconnected-(J19CX-MS-Pad2-C14)") (class "Default")
      (node (ref "J19") (pin "2-C14") (pinfunction "MS_2-C14") (pintype "passive"))
    )
    (net (code "135") (name "unconnected-(J19CY-MS-Pad2-C15)") (class "Default")
      (node (ref "J19") (pin "2-C15") (pinfunction "MS_2-C15") (pintype "passive"))
    )
    (net (code "136") (name "unconnected-(J19CZ-MS-Pad2-C16)") (class "Default")
      (node (ref "J19") (pin "2-C16") (pinfunction "MS_2-C16") (pintype "passive"))
    )
    (net (code "137") (name "unconnected-(J19D-MS-Pad1-A12)") (class "Default")
      (node (ref "J19") (pin "1-A12") (pinfunction "MS_1-A12") (pintype "passive"))
    )
    (net (code "138") (name "unconnected-(J19DA-MS-Pad2-C17)") (class "Default")
      (node (ref "J19") (pin "2-C17") (pinfunction "MS_2-C17") (pintype "passive"))
    )
    (net (code "139") (name "unconnected-(J19DB-MS-Pad2-C18)") (class "Default")
      (node (ref "J19") (pin "2-C18") (pinfunction "MS_2-C18") (pintype "passive"))
    )
    (net (code "140") (name "unconnected-(J19DC-MS-Pad2-C19)") (class "Default")
      (node (ref "J19") (pin "2-C19") (pinfunction "MS_2-C19") (pintype "passive"))
    )
    (net (code "141") (name "unconnected-(J19DD-MS-Pad2-C2)") (class "Default")
      (node (ref "J19") (pin "2-C2") (pinfunction "MS_2-C2") (pintype "passive"))
    )
    (net (code "142") (name "unconnected-(J19DE-MS-Pad2-C20)") (class "Default")
      (node (ref "J19") (pin "2-C20") (pinfunction "MS_2-C20") (pintype "passive"))
    )
    (net (code "143") (name "unconnected-(J19DF-MS-Pad2-C21)") (class "Default")
      (node (ref "J19") (pin "2-C21") (pinfunction "MS_2-C21") (pintype "passive"))
    )
    (net (code "144") (name "unconnected-(J19DG-MS-Pad2-C22)") (class "Default")
      (node (ref "J19") (pin "2-C22") (pinfunction "MS_2-C22") (pintype "passive"))
    )
    (net (code "145") (name "unconnected-(J19DH-MS-Pad2-C23)") (class "Default")
      (node (ref "J19") (pin "2-C23") (pinfunction "MS_2-C23") (pintype "passive"))
    )
    (net (code "146") (name "unconnected-(J19DI-MS-Pad2-C24)") (class "Default")
      (node (ref "J19") (pin "2-C24") (pinfunction "MS_2-C24") (pintype "passive"))
    )
    (net (code "147") (name "unconnected-(J19DJ-MS-Pad2-C25)") (class "Default")
      (node (ref "J19") (pin "2-C25") (pinfunction "MS_2-C25") (pintype "passive"))
    )
    (net (code "148") (name "unconnected-(J19DK-MS-Pad2-C26)") (class "Default")
      (node (ref "J19") (pin "2-C26") (pinfunction "MS_2-C26") (pintype "passive"))
    )
    (net (code "149") (name "unconnected-(J19DL-MS-Pad2-C27)") (class "Default")
      (node (ref "J19") (pin "2-C27") (pinfunction "MS_2-C27") (pintype "passive"))
    )
    (net (code "150") (name "unconnected-(J19DM-MS-Pad2-C28)") (class "Default")
      (node (ref "J19") (pin "2-C28") (pinfunction "MS_2-C28") (pintype "passive"))
    )
    (net (code "151") (name "unconnected-(J19DN-MS-Pad2-C29)") (class "Default")
      (node (ref "J19") (pin "2-C29") (pinfunction "MS_2-C29") (pintype "passive"))
    )
    (net (code "152") (name "unconnected-(J19DO-MS-Pad2-C3)") (class "Default")
      (node (ref "J19") (pin "2-C3") (pinfunction "MS_2-C3") (pintype "passive"))
    )
    (net (code "153") (name "unconnected-(J19DP-MS-Pad2-C30)") (class "Default")
      (node (ref "J19") (pin "2-C30") (pinfunction "MS_2-C30") (pintype "passive"))
    )
    (net (code "154") (name "unconnected-(J19DQ-MS-Pad2-C31)") (class "Default")
      (node (ref "J19") (pin "2-C31") (pinfunction "MS_2-C31") (pintype "passive"))
    )
    (net (code "155") (name "unconnected-(J19DS-MS-Pad2-C4)") (class "Default")
      (node (ref "J19") (pin "2-C4") (pinfunction "MS_2-C4") (pintype "passive"))
    )
    (net (code "156") (name "unconnected-(J19DT-MS-Pad2-C5)") (class "Default")
      (node (ref "J19") (pin "2-C5") (pinfunction "MS_2-C5") (pintype "passive"))
    )
    (net (code "157") (name "unconnected-(J19DU-MS-Pad2-C6)") (class "Default")
      (node (ref "J19") (pin "2-C6") (pinfunction "MS_2-C6") (pintype "passive"))
    )
    (net (code "158") (name "unconnected-(J19DV-MS-Pad2-C7)") (class "Default")
      (node (ref "J19") (pin "2-C7") (pinfunction "MS_2-C7") (pintype "passive"))
    )
    (net (code "159") (name "unconnected-(J19DW-MS-Pad2-C8)") (class "Default")
      (node (ref "J19") (pin "2-C8") (pinfunction "MS_2-C8") (pintype "passive"))
    )
    (net (code "160") (name "unconnected-(J19E-MS-Pad1-A13)") (class "Default")
      (node (ref "J19") (pin "1-A13") (pinfunction "MS_1-A13") (pintype "passive"))
    )
    (net (code "161") (name "unconnected-(J19F-MS-Pad1-A14)") (class "Default")
      (node (ref "J19") (pin "1-A14") (pinfunction "MS_1-A14") (pintype "passive"))
    )
    (net (code "162") (name "unconnected-(J19G-MS-Pad1-A15)") (class "Default")
      (node (ref "J19") (pin "1-A15") (pinfunction "MS_1-A15") (pintype "passive"))
    )
    (net (code "163") (name "unconnected-(J19H-MS-Pad1-A16)") (class "Default")
      (node (ref "J19") (pin "1-A16") (pinfunction "MS_1-A16") (pintype "passive"))
    )
    (net (code "164") (name "unconnected-(J19I-MS-Pad1-A17)") (class "Default")
      (node (ref "J19") (pin "1-A17") (pinfunction "MS_1-A17") (pintype "passive"))
    )
    (net (code "165") (name "unconnected-(J19J-MS-Pad1-A18)") (class "Default")
      (node (ref "J19") (pin "1-A18") (pinfunction "MS_1-A18") (pintype "passive"))
    )
    (net (code "166") (name "unconnected-(J19K-MS-Pad1-A19)") (class "Default")
      (node (ref "J19") (pin "1-A19") (pinfunction "MS_1-A19") (pintype "passive"))
    )
    (net (code "167") (name "unconnected-(J19L-MS-Pad1-A2)") (class "Default")
      (node (ref "J19") (pin "1-A2") (pinfunction "MS_1-A2") (pintype "passive"))
    )
    (net (code "168") (name "unconnected-(J19M-MS-Pad1-A20)") (class "Default")
      (node (ref "J19") (pin "1-A20") (pinfunction "MS_1-A20") (pintype "passive"))
    )
    (net (code "169") (name "unconnected-(J19N-MS-Pad1-A21)") (class "Default")
      (node (ref "J19") (pin "1-A21") (pinfunction "MS_1-A21") (pintype "passive"))
    )
    (net (code "170") (name "unconnected-(J19O-MS-Pad1-A22)") (class "Default")
      (node (ref "J19") (pin "1-A22") (pinfunction "MS_1-A22") (pintype "passive"))
    )
    (net (code "171") (name "unconnected-(J19P-MS-Pad1-A23)") (class "Default")
      (node (ref "J19") (pin "1-A23") (pinfunction "MS_1-A23") (pintype "passive"))
    )
    (net (code "172") (name "unconnected-(J19Q-MS-Pad1-A24)") (class "Default")
      (node (ref "J19") (pin "1-A24") (pinfunction "MS_1-A24") (pintype "passive"))
    )
    (net (code "173") (name "unconnected-(J19R-MS-Pad1-A25)") (class "Default")
      (node (ref "J19") (pin "1-A25") (pinfunction "MS_1-A25") (pintype "passive"))
    )
    (net (code "174") (name "unconnected-(J19S-MS-Pad1-A26)") (class "Default")
      (node (ref "J19") (pin "1-A26") (pinfunction "MS_1-A26") (pintype "passive"))
    )
    (net (code "175") (name "unconnected-(J19T-MS-Pad1-A27)") (class "Default")
      (node (ref "J19") (pin "1-A27") (pinfunction "MS_1-A27") (pintype "passive"))
    )
    (net (code "176") (name "unconnected-(J19U-MS-Pad1-A28)") (class "Default")
      (node (ref "J19") (pin "1-A28") (pinfunction "MS_1-A28") (pintype "passive"))
    )
    (net (code "177") (name "unconnected-(J19V-MS-Pad1-A29)") (class "Default")
      (node (ref "J19") (pin "1-A29") (pinfunction "MS_1-A29") (pintype "passive"))
    )
    (net (code "178") (name "unconnected-(J19W-MS-Pad1-A3)") (class "Default")
      (node (ref "J19") (pin "1-A3") (pinfunction "MS_1-A3") (pintype "passive"))
    )
    (net (code "179") (name "unconnected-(J19X-MS-Pad1-A30)") (class "Default")
      (node (ref "J19") (pin "1-A30") (pinfunction "MS_1-A30") (pintype "passive"))
    )
    (net (code "180") (name "unconnected-(J19Y-MS-Pad1-A31)") (class "Default")
      (node (ref "J19") (pin "1-A31") (pinfunction "MS_1-A31") (pintype "passive"))
    )
    (net (code "181") (name "unconnected-(X13C-S-Pad11)") (class "Default")
      (node (ref "X13") (pin "11") (pinfunction "S_11") (pintype "passive"))
    )
    (net (code "182") (name "unconnected-(X13E-S-Pad13)") (class "Default")
      (node (ref "X13") (pin "13") (pinfunction "S_13") (pintype "passive"))
    )
    (net (code "183") (name "unconnected-(X13G-S-Pad15)") (class "Default")
      (node (ref "X13") (pin "15") (pinfunction "S_15") (pintype "passive"))
    )
    (net (code "184") (name "unconnected-(X13I-S-Pad17)") (class "Default")
      (node (ref "X13") (pin "17") (pinfunction "S_17") (pintype "passive"))
    )
    (net (code "185") (name "unconnected-(X13K-S-Pad19)") (class "Default")
      (node (ref "X13") (pin "19") (pinfunction "S_19") (pintype "passive"))
    )
    (net (code "186") (name "unconnected-(X13N-S-Pad21)") (class "Default")
      (node (ref "X13") (pin "21") (pinfunction "S_21") (pintype "passive"))
    )
    (net (code "187") (name "unconnected-(X13R-S-Pad25)") (class "Default")
      (node (ref "X13") (pin "25") (pinfunction "S_25") (pintype "passive"))
    )
    (net (code "188") (name "unconnected-(X13T-S-Pad27)") (class "Default")
      (node (ref "X13") (pin "27") (pinfunction "S_27") (pintype "passive"))
    )
    (net (code "189") (name "unconnected-(X14A-S-Pad1)") (class "Default")
      (node (ref "X14") (pin "1") (pinfunction "S_1") (pintype "passive"))
    )
    (net (code "190") (name "unconnected-(X14AA-S-Pad8)") (class "Default")
      (node (ref "X14") (pin "8") (pinfunction "S_8") (pintype "passive"))
    )
    (net (code "191") (name "unconnected-(X14AB-S-Pad9)") (class "Default")
      (node (ref "X14") (pin "9") (pinfunction "S_9") (pintype "passive"))
    )
    (net (code "192") (name "unconnected-(X14B-S-Pad10)") (class "Default")
      (node (ref "X14") (pin "10") (pinfunction "S_10") (pintype "passive"))
    )
    (net (code "193") (name "unconnected-(X14C-S-Pad11)") (class "Default")
      (node (ref "X14") (pin "11") (pinfunction "S_11") (pintype "passive"))
    )
    (net (code "194") (name "unconnected-(X14D-S-Pad12)") (class "Default")
      (node (ref "X14") (pin "12") (pinfunction "S_12") (pintype "passive"))
    )
    (net (code "195") (name "unconnected-(X14E-S-Pad13)") (class "Default")
      (node (ref "X14") (pin "13") (pinfunction "S_13") (pintype "passive"))
    )
    (net (code "196") (name "unconnected-(X14F-S-Pad14)") (class "Default")
      (node (ref "X14") (pin "14") (pinfunction "S_14") (pintype "passive"))
    )
    (net (code "197") (name "unconnected-(X14G-S-Pad15)") (class "Default")
      (node (ref "X14") (pin "15") (pinfunction "S_15") (pintype "passive"))
    )
    (net (code "198") (name "unconnected-(X14H-S-Pad16)") (class "Default")
      (node (ref "X14") (pin "16") (pinfunction "S_16") (pintype "passive"))
    )
    (net (code "199") (name "unconnected-(X14I-S-Pad17)") (class "Default")
      (node (ref "X14") (pin "17") (pinfunction "S_17") (pintype "passive"))
    )
    (net (code "200") (name "unconnected-(X14J-S-Pad18)") (class "Default")
      (node (ref "X14") (pin "18") (pinfunction "S_18") (pintype "passive"))
    )
    (net (code "201") (name "unconnected-(X14K-S-Pad19)") (class "Default")
      (node (ref "X14") (pin "19") (pinfunction "S_19") (pintype "passive"))
    )
    (net (code "202") (name "unconnected-(X14L-S-Pad2)") (class "Default")
      (node (ref "X14") (pin "2") (pinfunction "S_2") (pintype "passive"))
    )
    (net (code "203") (name "unconnected-(X14M-S-Pad20)") (class "Default")
      (node (ref "X14") (pin "20") (pinfunction "S_20") (pintype "passive"))
    )
    (net (code "204") (name "unconnected-(X14N-S-Pad21)") (class "Default")
      (node (ref "X14") (pin "21") (pinfunction "S_21") (pintype "passive"))
    )
    (net (code "205") (name "unconnected-(X14O-S-Pad22)") (class "Default")
      (node (ref "X14") (pin "22") (pinfunction "S_22") (pintype "passive"))
    )
    (net (code "206") (name "unconnected-(X14P-S-Pad23)") (class "Default")
      (node (ref "X14") (pin "23") (pinfunction "S_23") (pintype "passive"))
    )
    (net (code "207") (name "unconnected-(X14Q-S-Pad24)") (class "Default")
      (node (ref "X14") (pin "24") (pinfunction "S_24") (pintype "passive"))
    )
    (net (code "208") (name "unconnected-(X14R-S-Pad25)") (class "Default")
      (node (ref "X14") (pin "25") (pinfunction "S_25") (pintype "passive"))
    )
    (net (code "209") (name "unconnected-(X14S-S-Pad26)") (class "Default")
      (node (ref "X14") (pin "26") (pinfunction "S_26") (pintype "passive"))
    )
    (net (code "210") (name "unconnected-(X14T-S-Pad27)") (class "Default")
      (node (ref "X14") (pin "27") (pinfunction "S_27") (pintype "passive"))
    )
    (net (code "211") (name "unconnected-(X14U-S-Pad28)") (class "Default")
      (node (ref "X14") (pin "28") (pinfunction "S_28") (pintype "passive"))
    )
    (net (code "212") (name "unconnected-(X14V-S-Pad3)") (class "Default")
      (node (ref "X14") (pin "3") (pinfunction "S_3") (pintype "passive"))
    )
    (net (code "213") (name "unconnected-(X14W-S-Pad4)") (class "Default")
      (node (ref "X14") (pin "4") (pinfunction "S_4") (pintype "passive"))
    )
    (net (code "214") (name "unconnected-(X14X-S-Pad5)") (class "Default")
      (node (ref "X14") (pin "5") (pinfunction "S_5") (pintype "passive"))
    )
    (net (code "215") (name "unconnected-(X14Y-S-Pad6)") (class "Default")
      (node (ref "X14") (pin "6") (pinfunction "S_6") (pintype "passive"))
    )
    (net (code "216") (name "unconnected-(X14Z-S-Pad7)") (class "Default")
      (node (ref "X14") (pin "7") (pinfunction "S_7") (pintype "passive"))
    )
    (net (code "217") (name "unconnected-(X15A-S-Pad1)") (class "Default")
      (node (ref "X15") (pin "1") (pinfunction "S_1") (pintype "passive"))
    )
    (net (code "218") (name "unconnected-(X15C-S-Pad11)") (class "Default")
      (node (ref "X15") (pin "11") (pinfunction "S_11") (pintype "passive"))
    )
    (net (code "219") (name "unconnected-(X15E-S-Pad13)") (class "Default")
      (node (ref "X15") (pin "13") (pinfunction "S_13") (pintype "passive"))
    )
    (net (code "220") (name "unconnected-(X15J-S-Pad3)") (class "Default")
      (node (ref "X15") (pin "3") (pinfunction "S_3") (pintype "passive"))
    )
    (net (code "221") (name "unconnected-(X15L-S-Pad5)") (class "Default")
      (node (ref "X15") (pin "5") (pinfunction "S_5") (pintype "passive"))
    )
    (net (code "222") (name "unconnected-(X15N-S-Pad7)") (class "Default")
      (node (ref "X15") (pin "7") (pinfunction "S_7") (pintype "passive"))
    )
    (net (code "223") (name "unconnected-(X15P-S-Pad9)") (class "Default")
      (node (ref "X15") (pin "9") (pinfunction "S_9") (pintype "passive"))
    )
    (net (code "224") (name "unconnected-(X16A-S-Pad1)") (class "Default")
      (node (ref "X16") (pin "1") (pinfunction "S_1") (pintype "passive"))
    )
    (net (code "225") (name "unconnected-(X16B-S-Pad10)") (class "Default")
      (node (ref "X16") (pin "10") (pinfunction "S_10") (pintype "passive"))
    )
    (net (code "226") (name "unconnected-(X16C-S-Pad11)") (class "Default")
      (node (ref "X16") (pin "11") (pinfunction "S_11") (pintype "passive"))
    )
    (net (code "227") (name "unconnected-(X16D-S-Pad12)") (class "Default")
      (node (ref "X16") (pin "12") (pinfunction "S_12") (pintype "passive"))
    )
    (net (code "228") (name "unconnected-(X16E-S-Pad13)") (class "Default")
      (node (ref "X16") (pin "13") (pinfunction "S_13") (pintype "passive"))
    )
    (net (code "229") (name "unconnected-(X16F-S-Pad14)") (class "Default")
      (node (ref "X16") (pin "14") (pinfunction "S_14") (pintype "passive"))
    )
    (net (code "230") (name "unconnected-(X16G-S-Pad15)") (class "Default")
      (node (ref "X16") (pin "15") (pinfunction "S_15") (pintype "passive"))
    )
    (net (code "231") (name "unconnected-(X16H-S-Pad16)") (class "Default")
      (node (ref "X16") (pin "16") (pinfunction "S_16") (pintype "passive"))
    )
    (net (code "232") (name "unconnected-(X16I-S-Pad2)") (class "Default")
      (node (ref "X16") (pin "2") (pinfunction "S_2") (pintype "passive"))
    )
    (net (code "233") (name "unconnected-(X16J-S-Pad3)") (class "Default")
      (node (ref "X16") (pin "3") (pinfunction "S_3") (pintype "passive"))
    )
    (net (code "234") (name "unconnected-(X16K-S-Pad4)") (class "Default")
      (node (ref "X16") (pin "4") (pinfunction "S_4") (pintype "passive"))
    )
    (net (code "235") (name "unconnected-(X16L-S-Pad5)") (class "Default")
      (node (ref "X16") (pin "5") (pinfunction "S_5") (pintype "passive"))
    )
    (net (code "236") (name "unconnected-(X16M-S-Pad6)") (class "Default")
      (node (ref "X16") (pin "6") (pinfunction "S_6") (pintype "passive"))
    )
    (net (code "237") (name "unconnected-(X16N-S-Pad7)") (class "Default")
      (node (ref "X16") (pin "7") (pinfunction "S_7") (pintype "passive"))
    )
    (net (code "238") (name "unconnected-(X16O-S-Pad8)") (class "Default")
      (node (ref "X16") (pin "8") (pinfunction "S_8") (pintype "passive"))
    )
    (net (code "239") (name "unconnected-(X16P-S-Pad9)") (class "Default")
      (node (ref "X16") (pin "9") (pinfunction "S_9") (pintype "passive"))
    )
    (net (code "240") (name "unconnected-(X17A-S-Pad1)") (class "Default")
      (node (ref "X17") (pin "1") (pinfunction "S_1") (pintype "passive"))
    )
    (net (code "241") (name "unconnected-(X17AB-S-Pad9)") (class "Default")
      (node (ref "X17") (pin "9") (pinfunction "S_9") (pintype "passive"))
    )
    (net (code "242") (name "unconnected-(X17B-S-Pad10)") (class "Default")
      (node (ref "X17") (pin "10") (pinfunction "S_10") (pintype "passive"))
    )
    (net (code "243") (name "unconnected-(X17C-S-Pad11)") (class "Default")
      (node (ref "X17") (pin "11") (pinfunction "S_11") (pintype "passive"))
    )
    (net (code "244") (name "unconnected-(X17D-S-Pad12)") (class "Default")
      (node (ref "X17") (pin "12") (pinfunction "S_12") (pintype "passive"))
    )
    (net (code "245") (name "unconnected-(X17E-S-Pad13)") (class "Default")
      (node (ref "X17") (pin "13") (pinfunction "S_13") (pintype "passive"))
    )
    (net (code "246") (name "unconnected-(X17F-S-Pad14)") (class "Default")
      (node (ref "X17") (pin "14") (pinfunction "S_14") (pintype "passive"))
    )
    (net (code "247") (name "unconnected-(X17G-S-Pad15)") (class "Default")
      (node (ref "X17") (pin "15") (pinfunction "S_15") (pintype "passive"))
    )
    (net (code "248") (name "unconnected-(X17H-S-Pad16)") (class "Default")
      (node (ref "X17") (pin "16") (pinfunction "S_16") (pintype "passive"))
    )
    (net (code "249") (name "unconnected-(X17I-S-Pad17)") (class "Default")
      (node (ref "X17") (pin "17") (pinfunction "S_17") (pintype "passive"))
    )
    (net (code "250") (name "unconnected-(X17J-S-Pad18)") (class "Default")
      (node (ref "X17") (pin "18") (pinfunction "S_18") (pintype "passive"))
    )
    (net (code "251") (name "unconnected-(X17K-S-Pad19)") (class "Default")
      (node (ref "X17") (pin "19") (pinfunction "S_19") (pintype "passive"))
    )
    (net (code "252") (name "unconnected-(X17M-S-Pad20)") (class "Default")
      (node (ref "X17") (pin "20") (pinfunction "S_20") (pintype "passive"))
    )
    (net (code "253") (name "unconnected-(X17N-S-Pad21)") (class "Default")
      (node (ref "X17") (pin "21") (pinfunction "S_21") (pintype "passive"))
    )
    (net (code "254") (name "unconnected-(X17O-S-Pad22)") (class "Default")
      (node (ref "X17") (pin "22") (pinfunction "S_22") (pintype "passive"))
    )
    (net (code "255") (name "unconnected-(X17P-S-Pad23)") (class "Default")
      (node (ref "X17") (pin "23") (pinfunction "S_23") (pintype "passive"))
    )
    (net (code "256") (name "unconnected-(X17Q-S-Pad24)") (class "Default")
      (node (ref "X17") (pin "24") (pinfunction "S_24") (pintype "passive"))
    )
    (net (code "257") (name "unconnected-(X17R-S-Pad25)") (class "Default")
      (node (ref "X17") (pin "25") (pinfunction "S_25") (pintype "passive"))
    )
    (net (code "258") (name "unconnected-(X17S-S-Pad26)") (class "Default")
      (node (ref "X17") (pin "26") (pinfunction "S_26") (pintype "passive"))
    )
    (net (code "259") (name "unconnected-(X17T-S-Pad27)") (class "Default")
      (node (ref "X17") (pin "27") (pinfunction "S_27") (pintype "passive"))
    )
    (net (code "260") (name "unconnected-(X17U-S-Pad28)") (class "Default")
      (node (ref "X17") (pin "28") (pinfunction "S_28") (pintype "passive"))
    )
    (net (code "261") (name "unconnected-(X17V-S-Pad3)") (class "Default")
      (node (ref "X17") (pin "3") (pinfunction "S_3") (pintype "passive"))
    )
    (net (code "262") (name "unconnected-(X17X-S-Pad5)") (class "Default")
      (node (ref "X17") (pin "5") (pinfunction "S_5") (pintype "passive"))
    )
    (net (code "263") (name "unconnected-(X17Z-S-Pad7)") (class "Default")
      (node (ref "X17") (pin "7") (pinfunction "S_7") (pintype "passive"))
    )
    (net (code "264") (name "unconnected-(X18AB-S-Pad9)") (class "Default")
      (node (ref "X18") (pin "9") (pinfunction "S_9") (pintype "passive"))
    )
    (net (code "265") (name "unconnected-(X18C-S-Pad11)") (class "Default")
      (node (ref "X18") (pin "11") (pinfunction "S_11") (pintype "passive"))
    )
    (net (code "266") (name "unconnected-(X18E-S-Pad13)") (class "Default")
      (node (ref "X18") (pin "13") (pinfunction "S_13") (pintype "passive"))
    )
    (net (code "267") (name "unconnected-(X18G-S-Pad15)") (class "Default")
      (node (ref "X18") (pin "15") (pinfunction "S_15") (pintype "passive"))
    )
    (net (code "268") (name "unconnected-(X18I-S-Pad17)") (class "Default")
      (node (ref "X18") (pin "17") (pinfunction "S_17") (pintype "passive"))
    )
    (net (code "269") (name "unconnected-(X18K-S-Pad19)") (class "Default")
      (node (ref "X18") (pin "19") (pinfunction "S_19") (pintype "passive"))
    )
    (net (code "270") (name "unconnected-(X18L-S-Pad2)") (class "Default")
      (node (ref "X18") (pin "2") (pinfunction "S_2") (pintype "passive"))
    )
    (net (code "271") (name "unconnected-(X18N-S-Pad21)") (class "Default")
      (node (ref "X18") (pin "21") (pinfunction "S_21") (pintype "passive"))
    )
    (net (code "272") (name "unconnected-(X18R-S-Pad25)") (class "Default")
      (node (ref "X18") (pin "25") (pinfunction "S_25") (pintype "passive"))
    )
    (net (code "273") (name "unconnected-(X18T-S-Pad27)") (class "Default")
      (node (ref "X18") (pin "27") (pinfunction "S_27") (pintype "passive"))
    )
    (net (code "274") (name "unconnected-(X18V-S-Pad3)") (class "Default")
      (node (ref "X18") (pin "3") (pinfunction "S_3") (pintype "passive"))
    )
    (net (code "275") (name "unconnected-(X18X-S-Pad5)") (class "Default")
      (node (ref "X18") (pin "5") (pinfunction "S_5") (pintype "passive"))
    )
    (net (code "276") (name "unconnected-(X18Z-S-Pad7)") (class "Default")
      (node (ref "X18") (pin "7") (pinfunction "S_7") (pintype "passive"))
    )
  )
)
